# sc.net
KiCad netlist of a schematic drawn in EAGLE
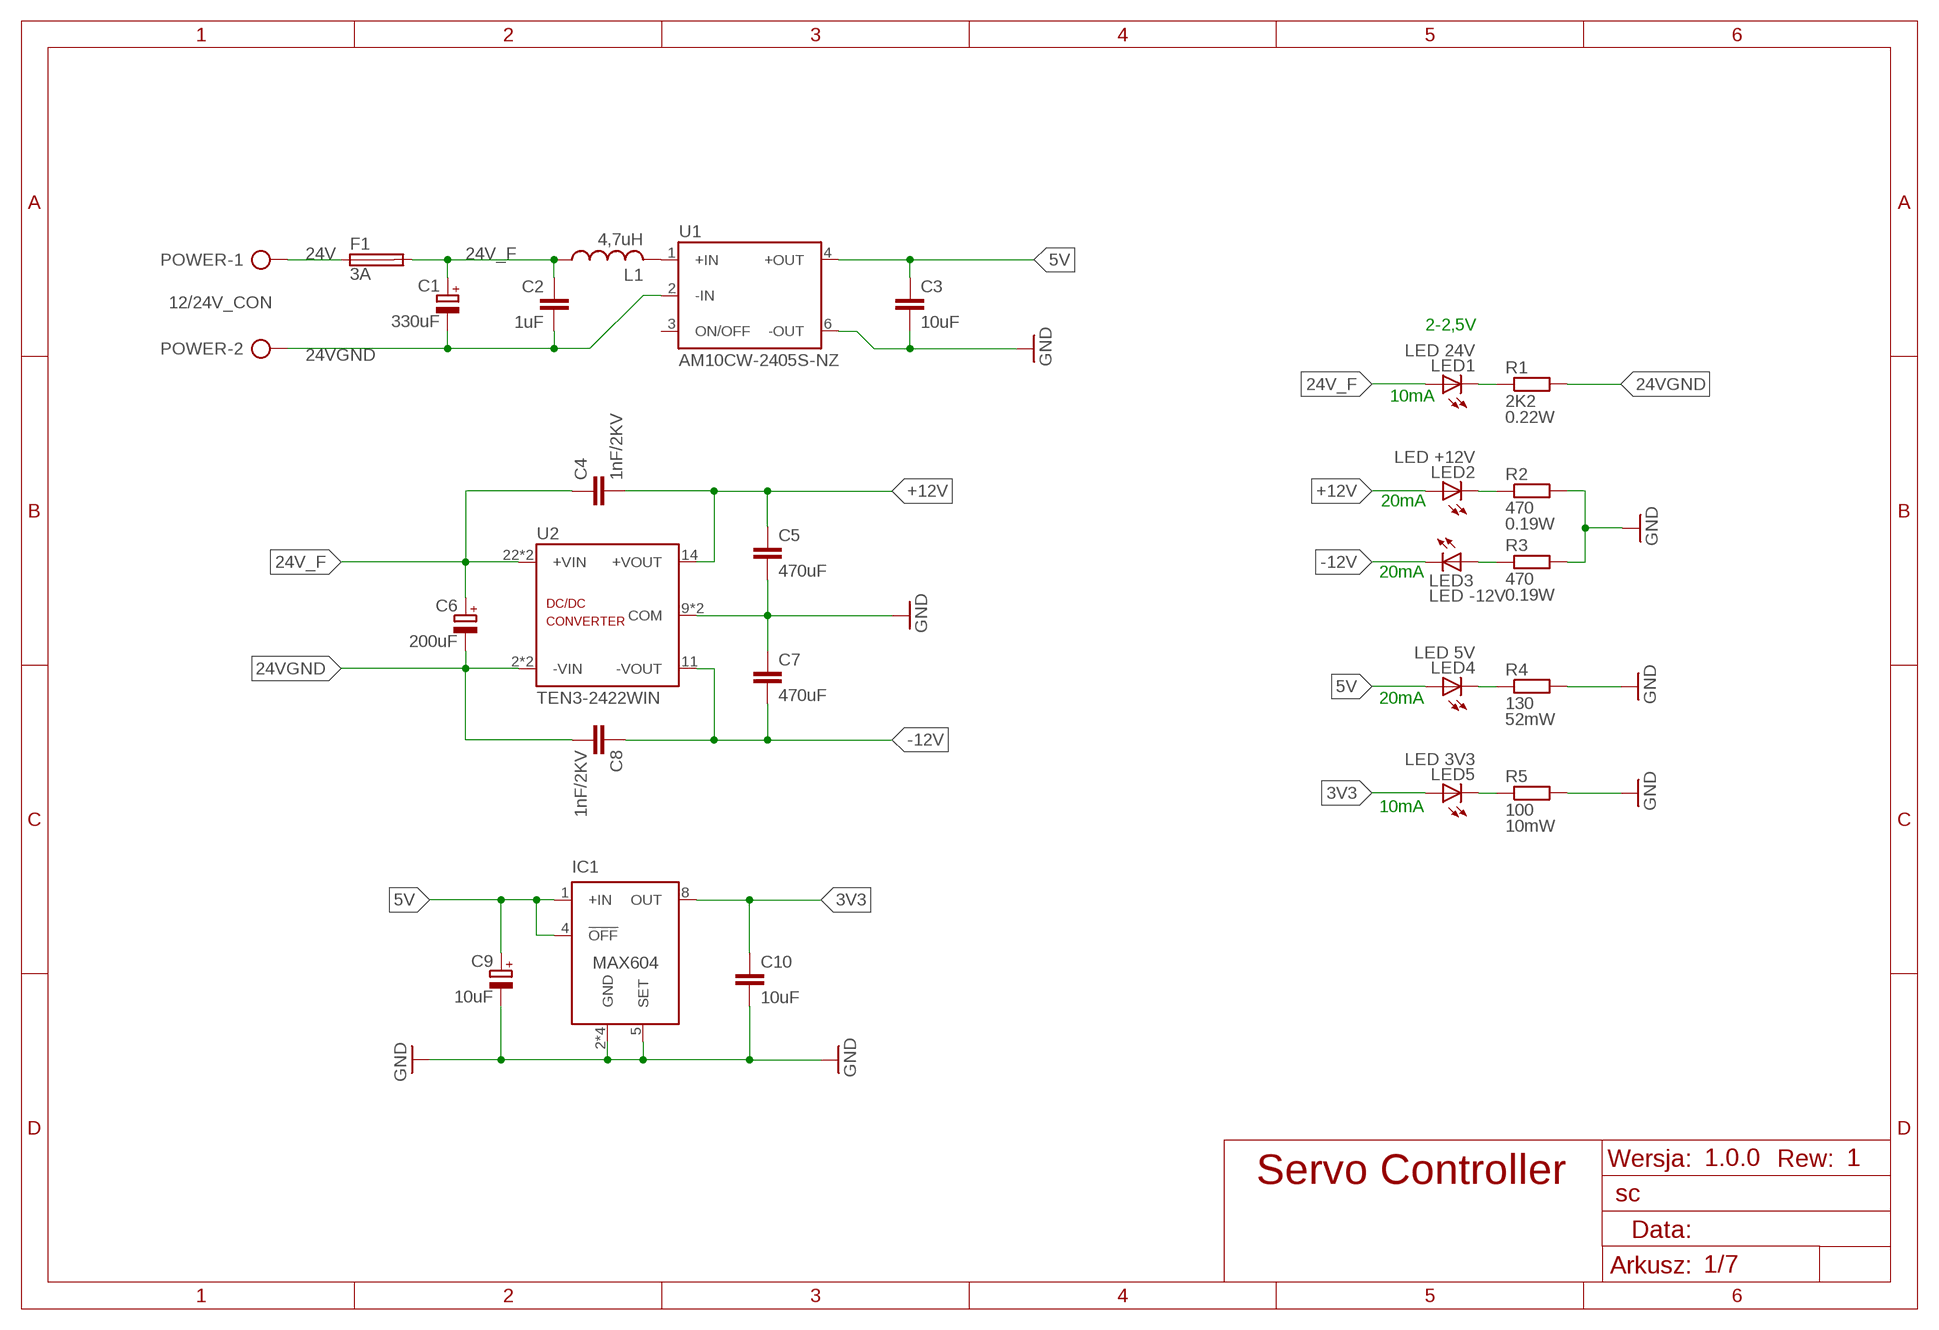
[diagram p0: schematic, sheet 1]
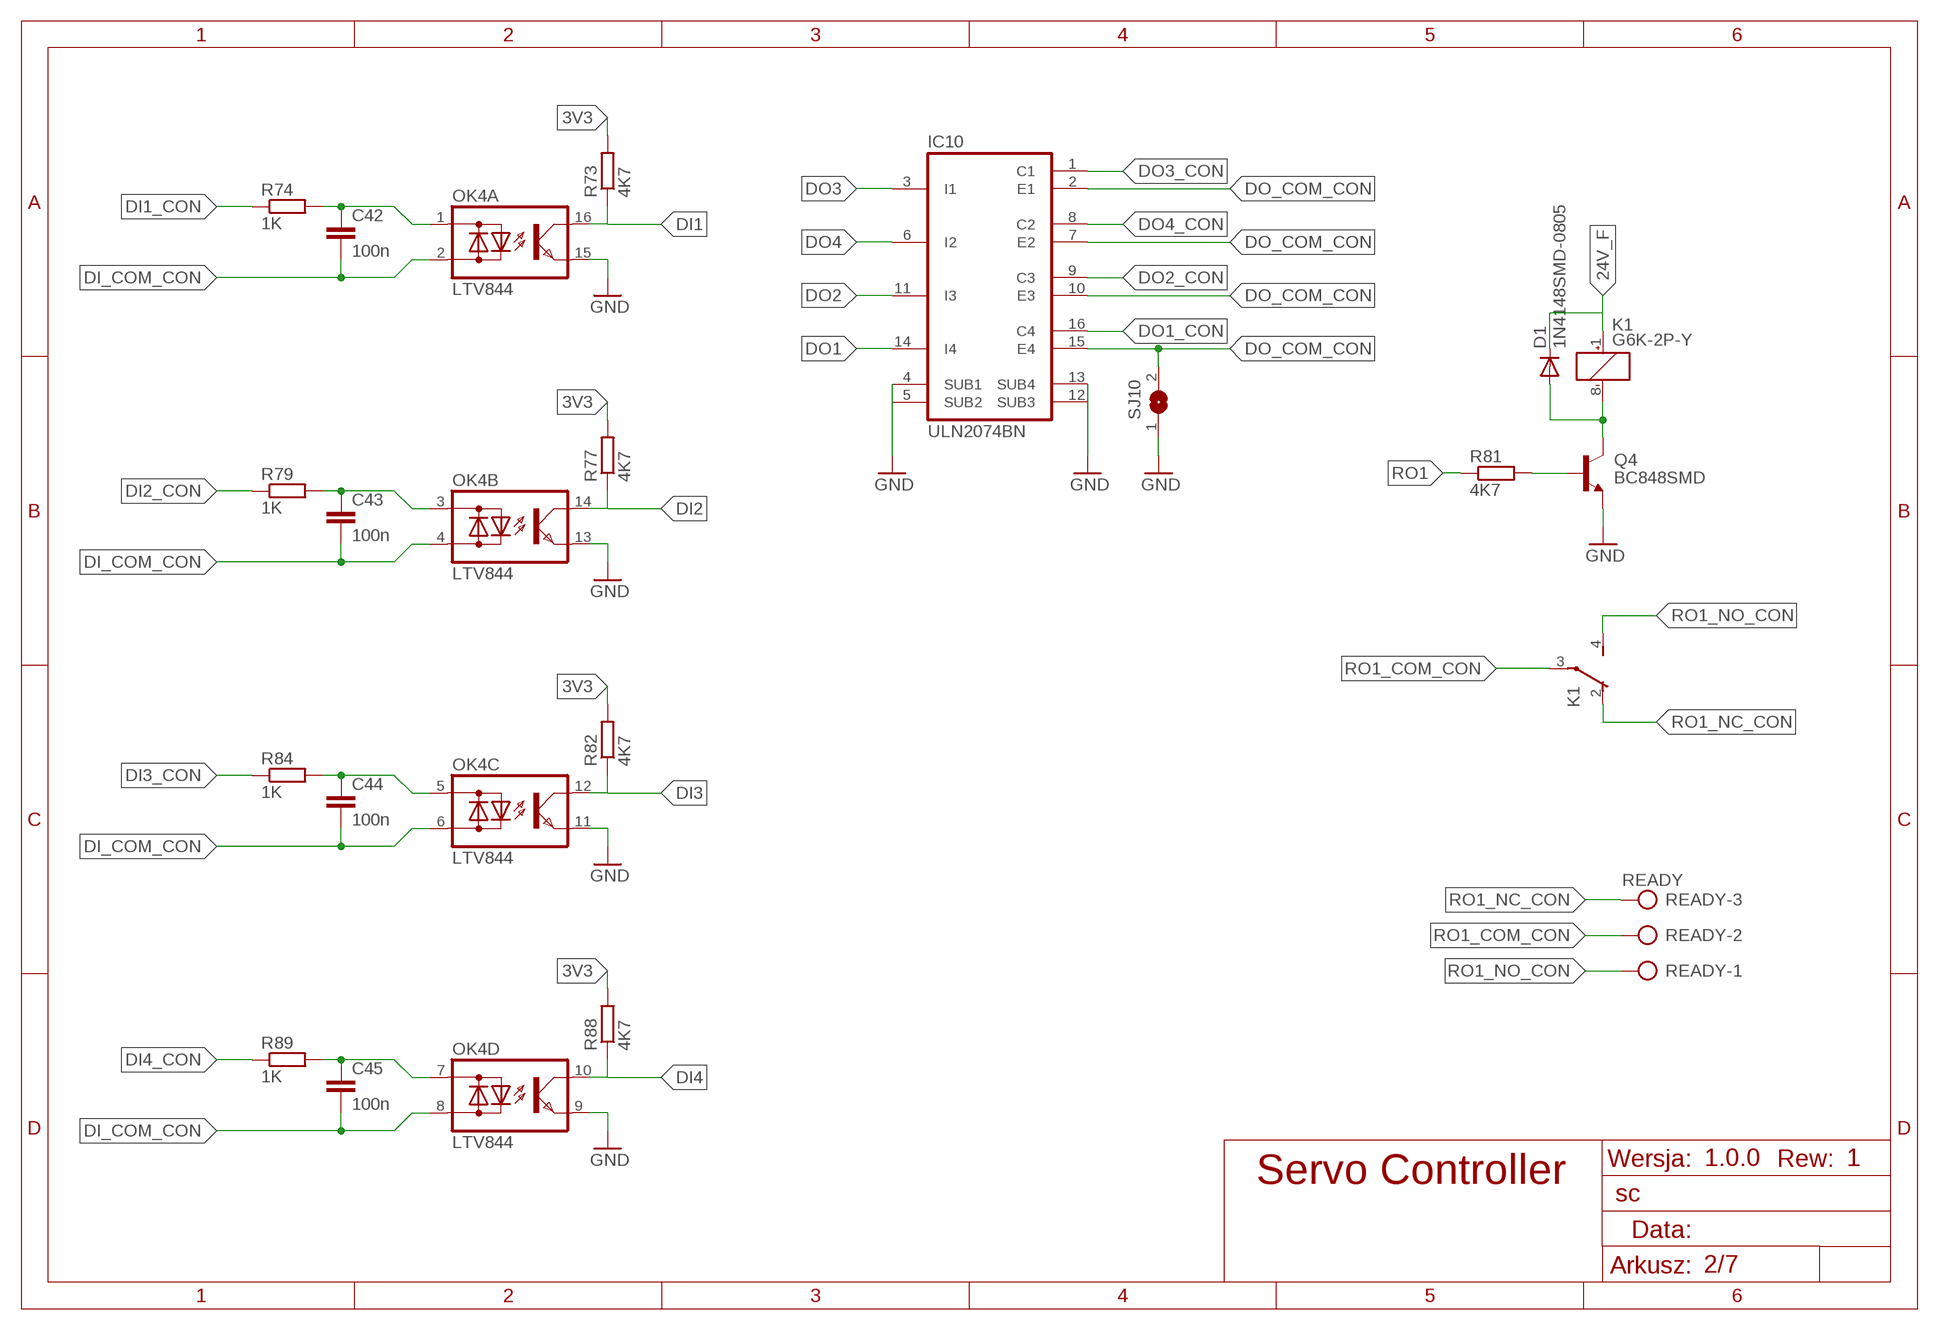
[diagram p1: schematic, sheet 2]
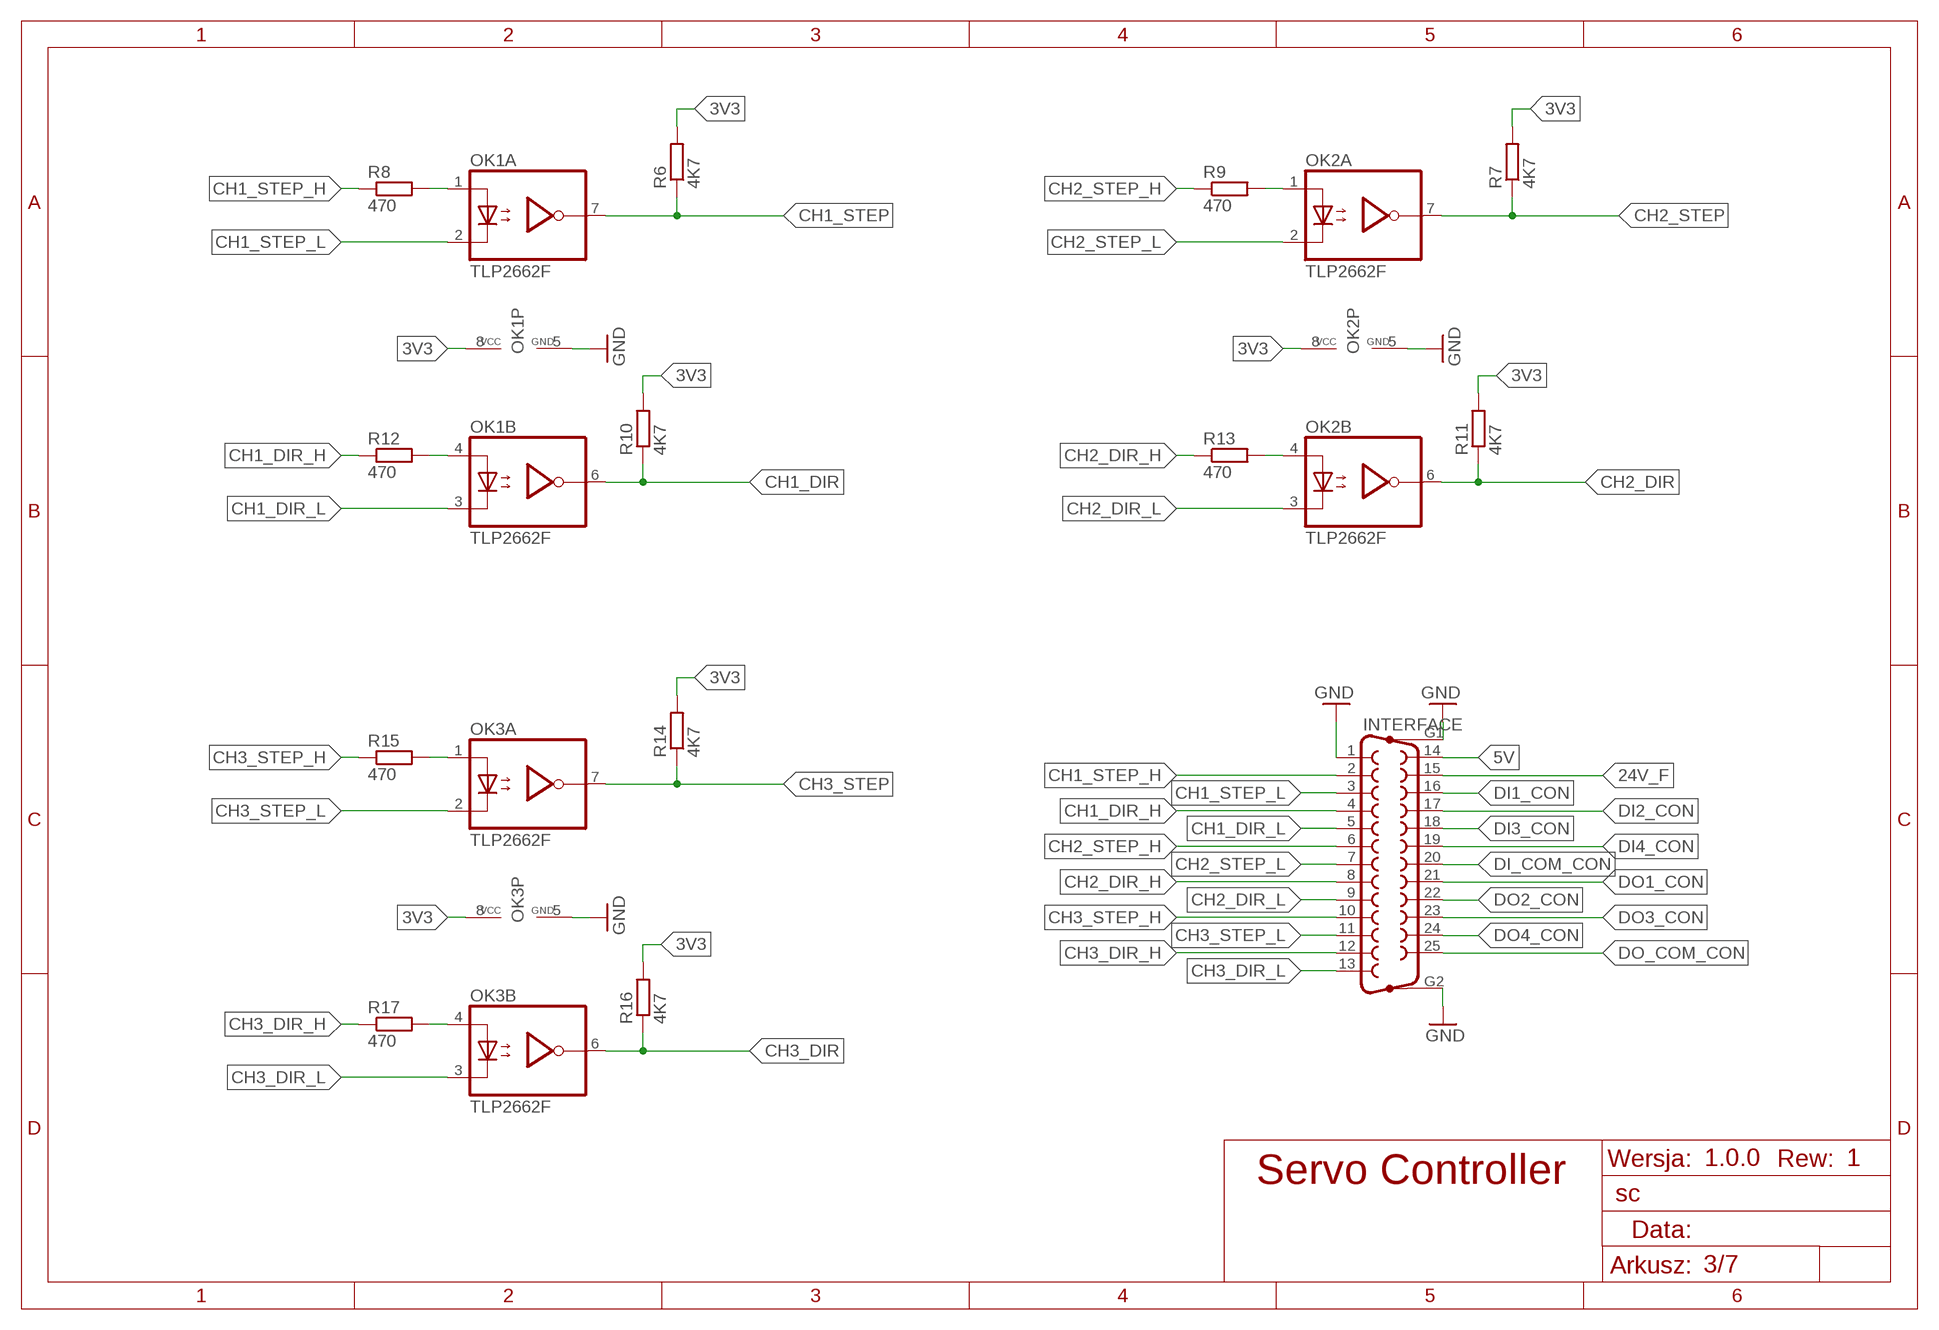
[diagram p2: schematic, sheet 3]
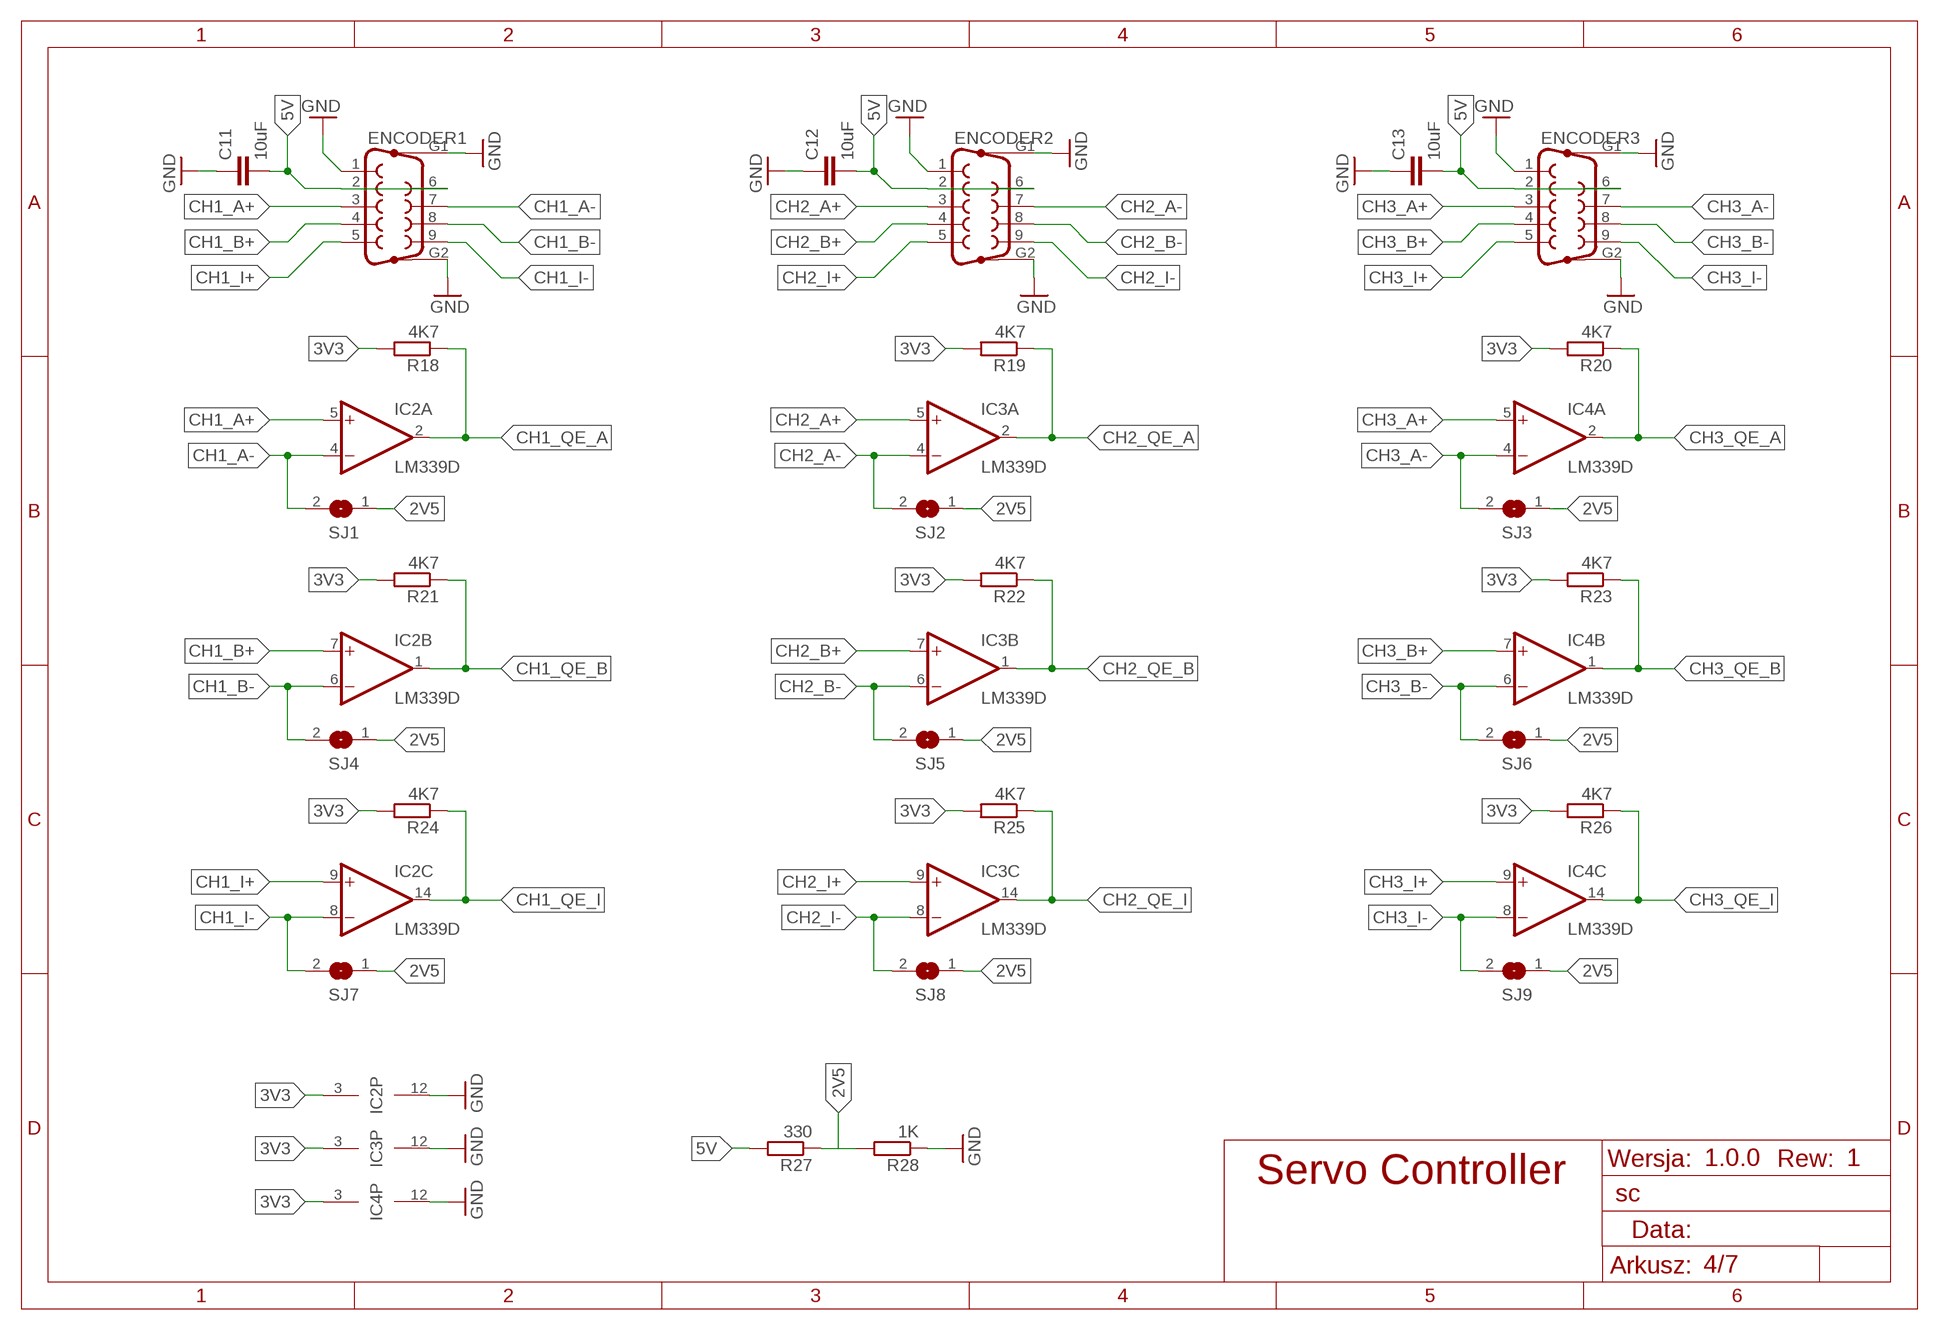
[diagram p3: schematic, sheet 4]
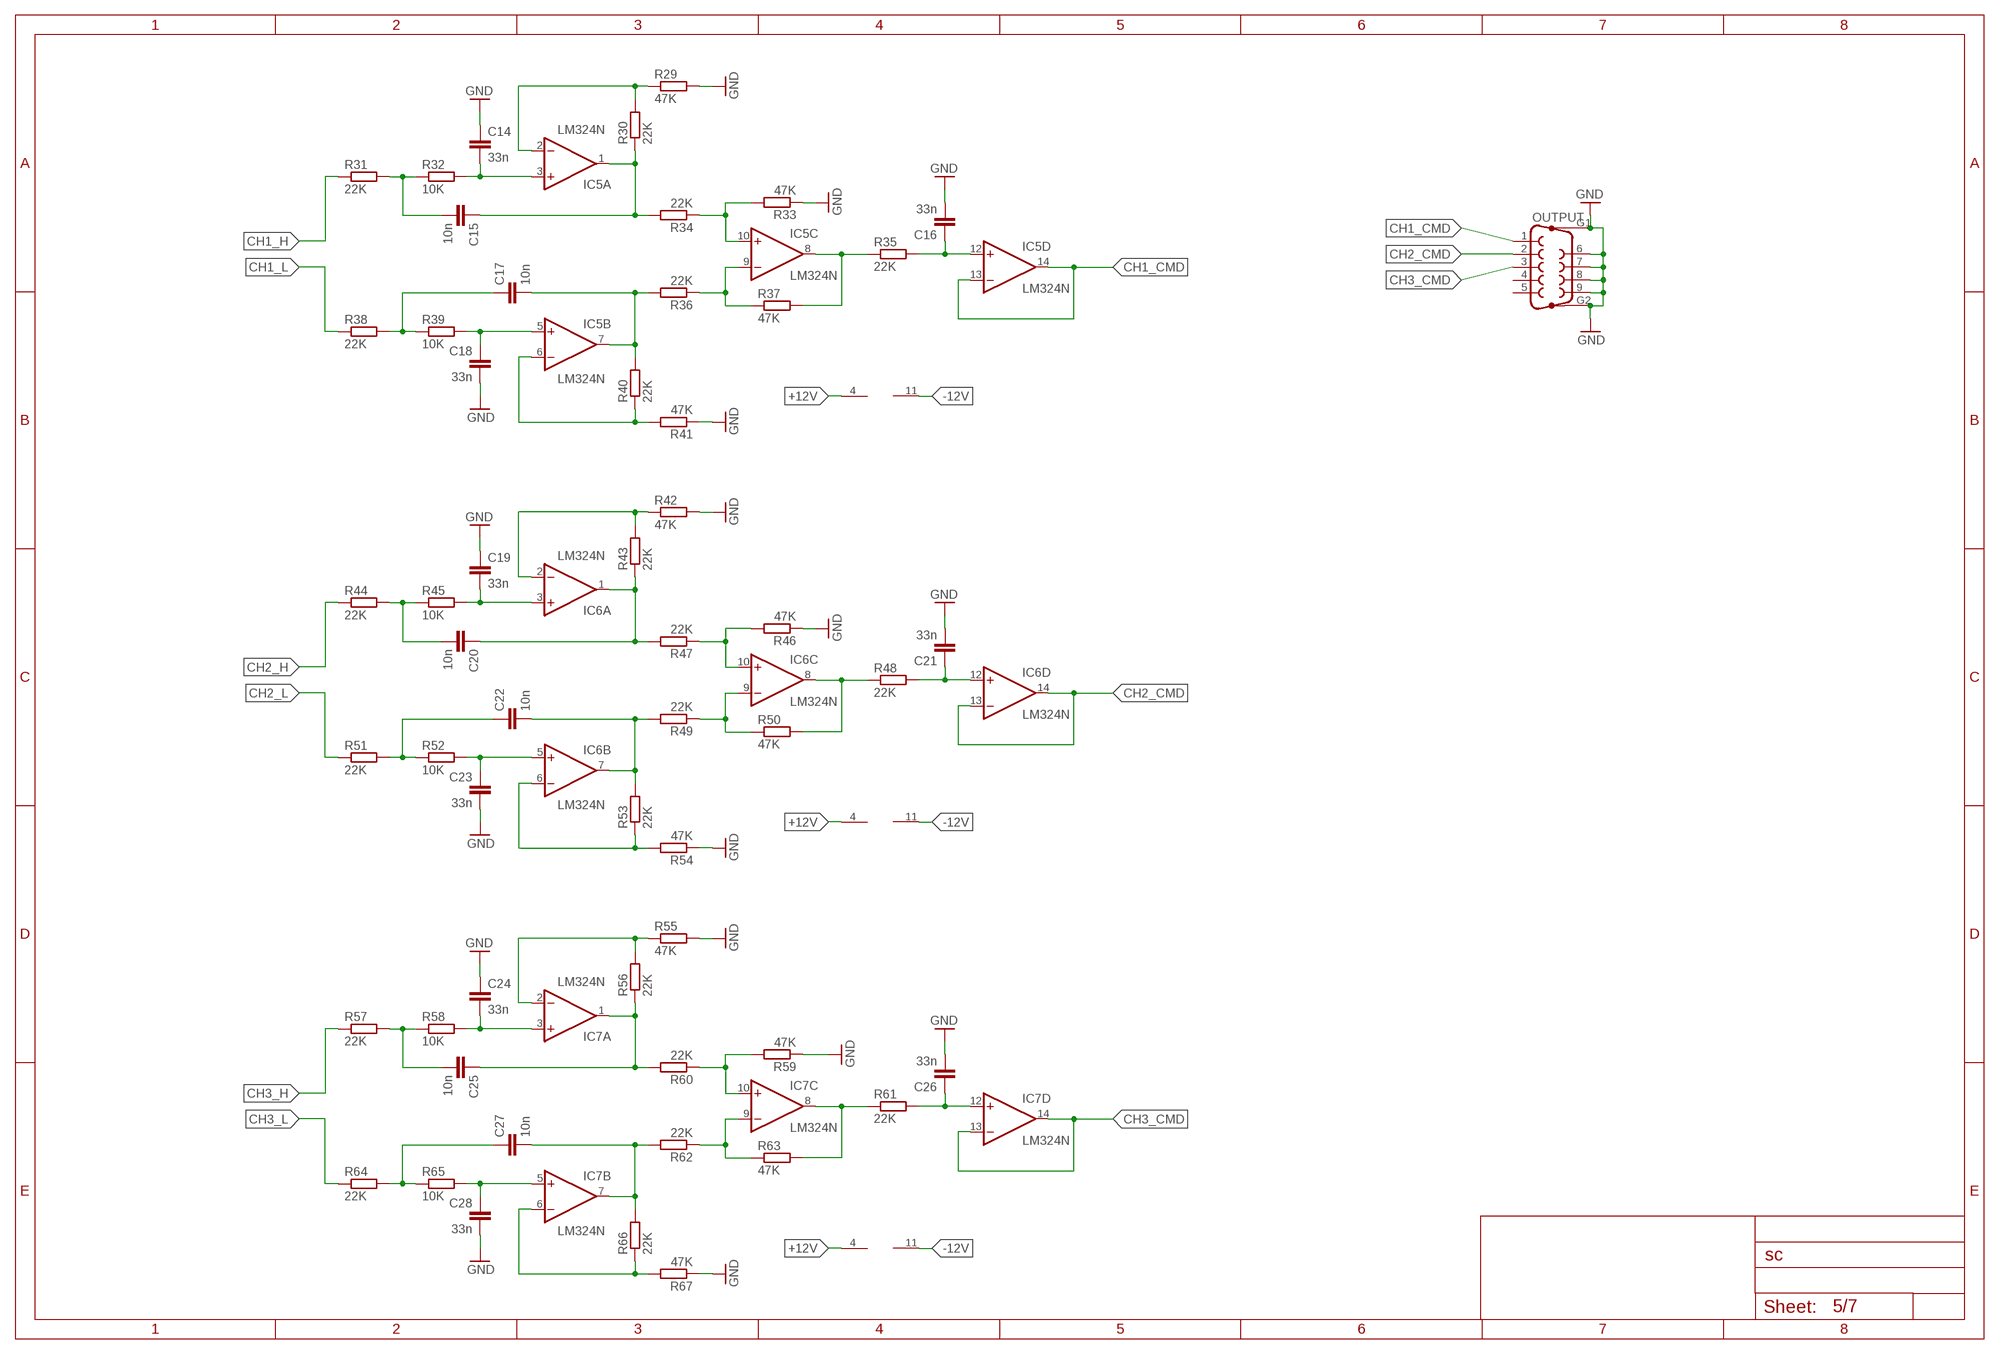
[diagram p4: schematic, sheet 5]
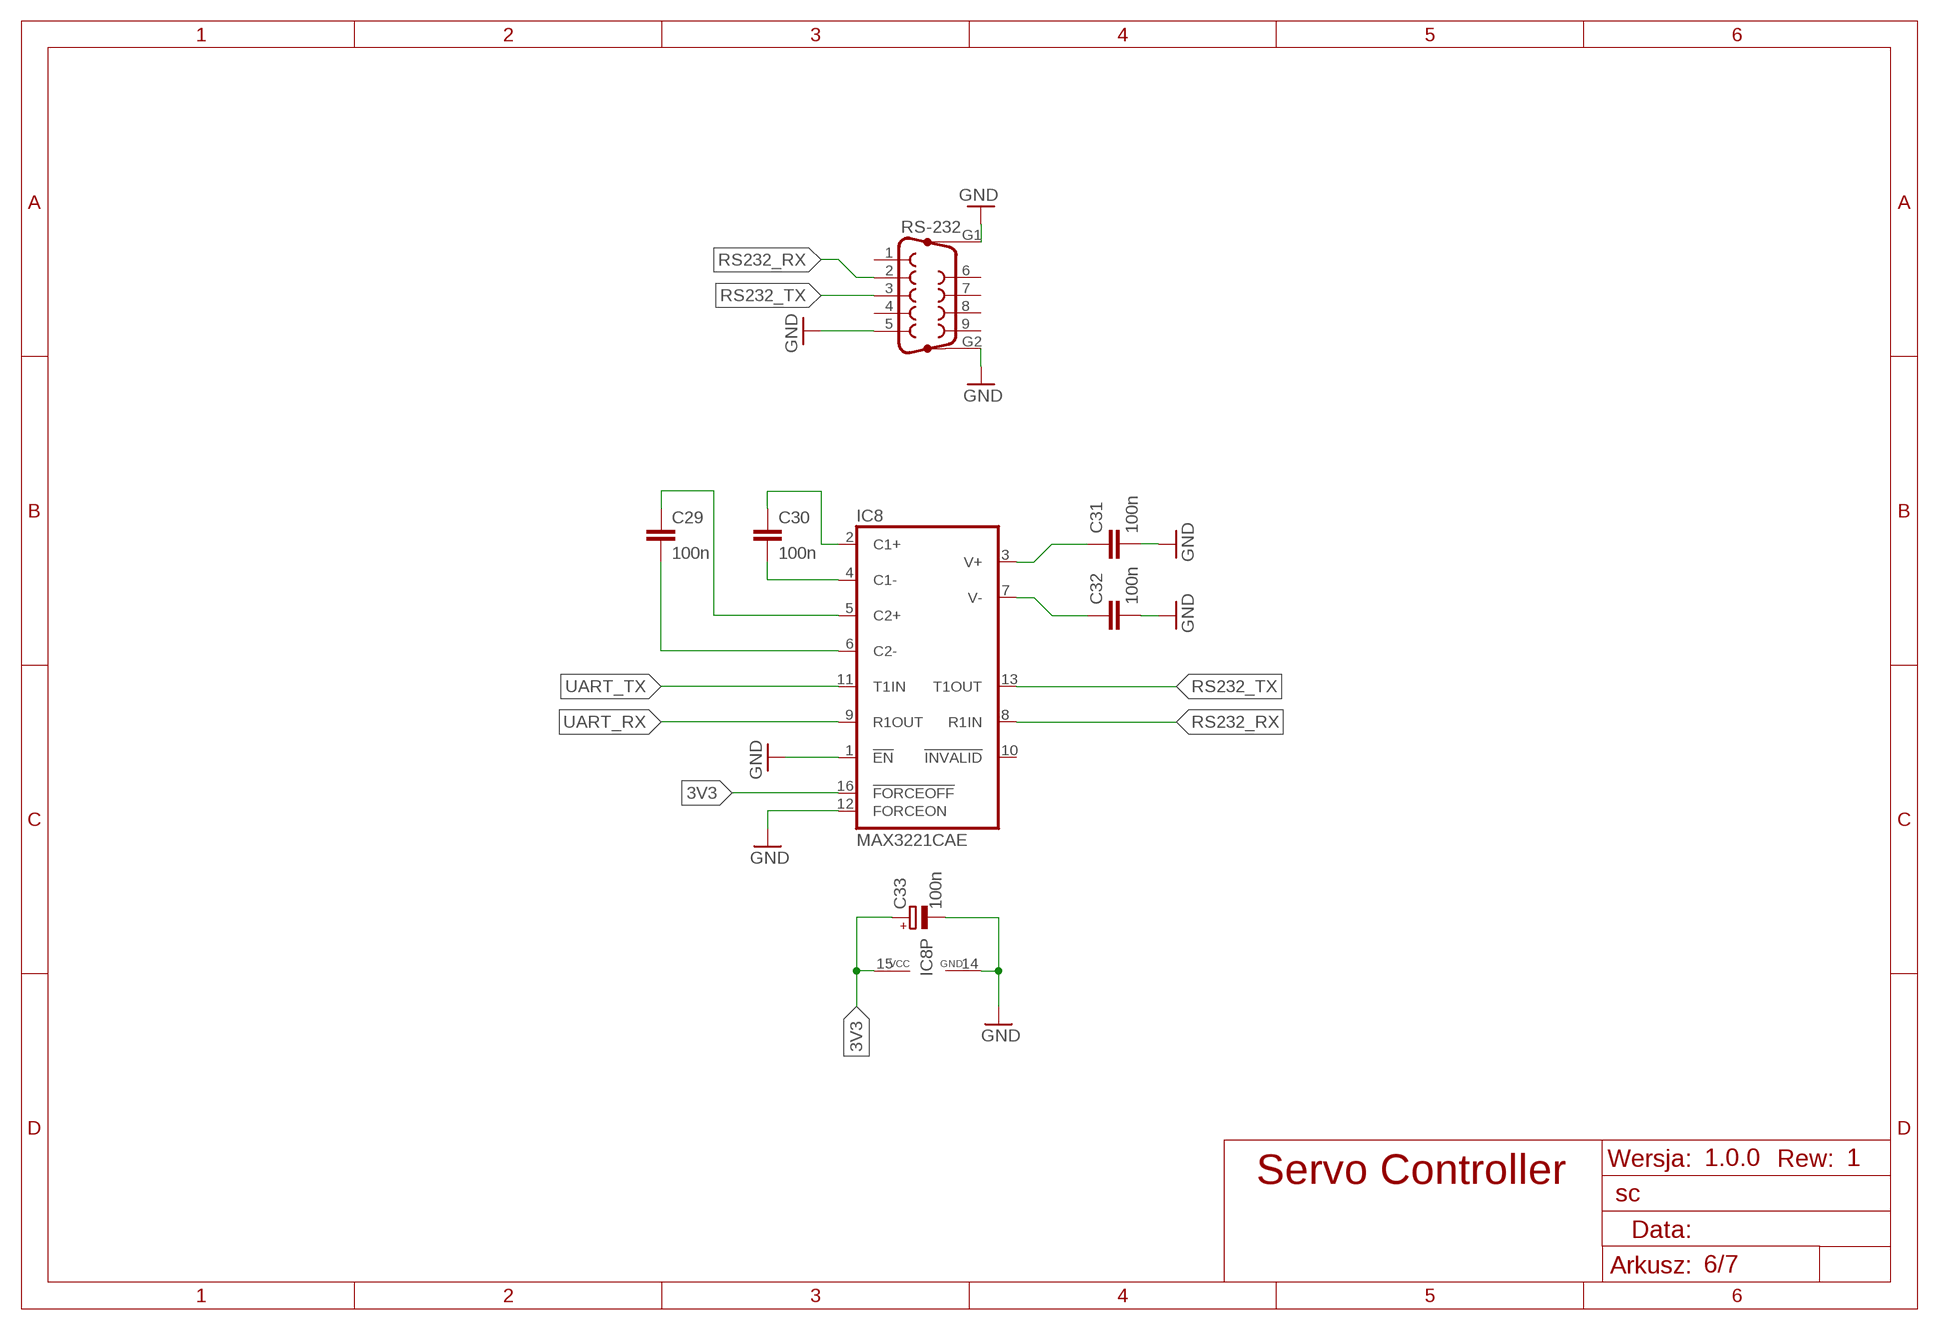
[diagram p5: schematic, sheet 6]
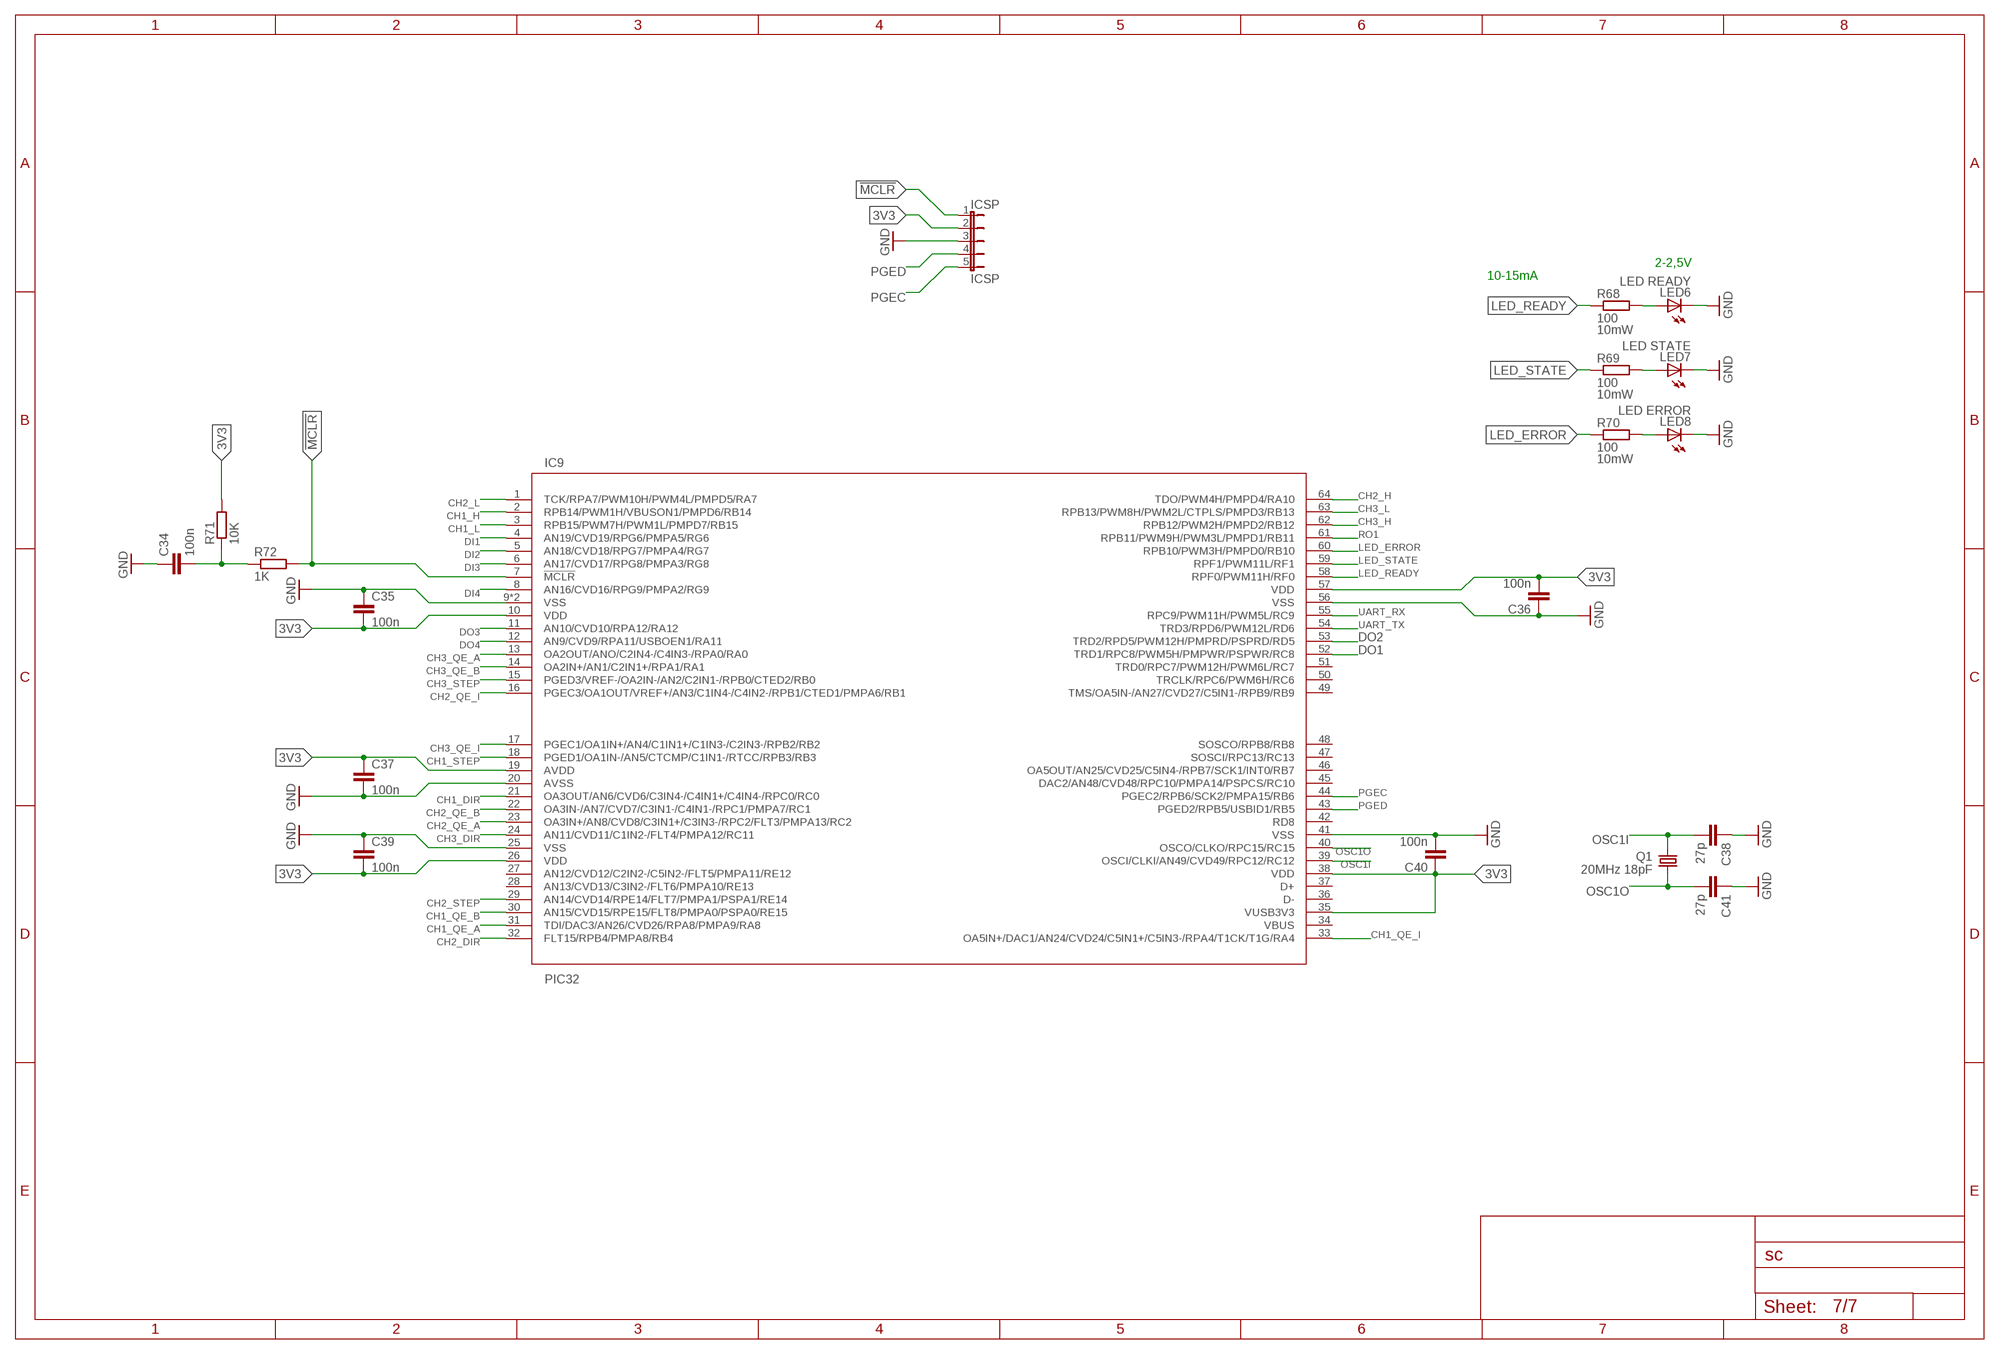
[diagram p6: schematic, sheet 7]

(export (version "E")
  (design (tool "Eeschema 10.0.6"))
  (components
    (comp (ref "C34")
      (value "100n")
      (footprint "eagle-import:C0805")
      (libsource (lib "eagle-import") (part "C-EUC0805"))
    )
    (comp (ref "C35")
      (value "100n")
      (footprint "eagle-import:C0805")
      (libsource (lib "eagle-import") (part "C-EUC0805"))
    )
    (comp (ref "C36")
      (value "100n")
      (footprint "eagle-import:C0805")
      (libsource (lib "eagle-import") (part "C-EUC0805"))
    )
    (comp (ref "C37")
      (value "100n")
      (footprint "eagle-import:C0805")
      (libsource (lib "eagle-import") (part "C-EUC0805"))
    )
    (comp (ref "C38")
      (value "27p")
      (footprint "eagle-import:C0805")
      (libsource (lib "eagle-import") (part "C-EUC0805"))
    )
    (comp (ref "C39")
      (value "100n")
      (footprint "eagle-import:C0805")
      (libsource (lib "eagle-import") (part "C-EUC0805"))
    )
    (comp (ref "C40")
      (value "100n")
      (footprint "eagle-import:C0805")
      (libsource (lib "eagle-import") (part "C-EUC0805"))
    )
    (comp (ref "C41")
      (value "27p")
      (footprint "eagle-import:C0805")
      (libsource (lib "eagle-import") (part "C-EUC0805"))
    )
    (comp (ref "IC9")
      (value "PIC32")
      (footprint "eagle-import:QFN64-9X9")
      (libsource (lib "eagle-import") (part "PIC32MK1024MCF0649X9MM"))
    )
    (comp (ref "ICSP")
      (value "ICSP")
      (footprint "eagle-import:JP5")
      (libsource (lib "eagle-import") (part "JP5E"))
    )
    (comp (ref "LED6")
      (value "LED READY")
      (footprint "eagle-import:SML1206")
      (libsource (lib "eagle-import") (part "LEDSML1206"))
    )
    (comp (ref "LED7")
      (value "LED STATE")
      (footprint "eagle-import:SML1206")
      (libsource (lib "eagle-import") (part "LEDSML1206"))
    )
    (comp (ref "LED8")
      (value "LED ERROR")
      (footprint "eagle-import:SML1206")
      (libsource (lib "eagle-import") (part "LEDSML1206"))
    )
    (comp (ref "Q1")
      (value "20MHz 18pF")
      (footprint "eagle-import:SM49")
      (libsource (lib "eagle-import") (part "CRYSTALSM49"))
    )
    (comp (ref "R68")
      (value "100")
      (footprint "eagle-import:R0805")
      (fields (field (name "POWER") "10mW"))
      (libsource (lib "eagle-import") (part "R-EU_R0805"))
    )
    (comp (ref "R69")
      (value "100")
      (footprint "eagle-import:R0805")
      (fields (field (name "POWER") "10mW"))
      (libsource (lib "eagle-import") (part "R-EU_R0805"))
    )
    (comp (ref "R70")
      (value "100")
      (footprint "eagle-import:R0805")
      (fields (field (name "POWER") "10mW"))
      (libsource (lib "eagle-import") (part "R-EU_R0805"))
    )
    (comp (ref "R71")
      (value "10K")
      (footprint "eagle-import:R0805")
      (libsource (lib "eagle-import") (part "R-EU_R0805"))
    )
    (comp (ref "R72")
      (value "1K")
      (footprint "eagle-import:R0805")
      (libsource (lib "eagle-import") (part "R-EU_R0805"))
    )
    (comp (ref "C1")
      (value "330uF")
      (footprint "eagle-import:E5-10,5")
      (libsource (lib "eagle-import") (part "CPOL-EUE5-10.5"))
    )
    (comp (ref "C2")
      (value "1uF")
      (footprint "eagle-import:C0805")
      (libsource (lib "eagle-import") (part "C-EUC0805"))
    )
    (comp (ref "C3")
      (value "10uF")
      (footprint "eagle-import:C0805")
      (libsource (lib "eagle-import") (part "C-EUC0805"))
    )
    (comp (ref "C4")
      (value "1nF/2KV")
      (footprint "eagle-import:C0805")
      (libsource (lib "eagle-import") (part "C-EUC0805"))
    )
    (comp (ref "C5")
      (value "470uF")
      (footprint "eagle-import:C0805")
      (libsource (lib "eagle-import") (part "C-EUC0805"))
    )
    (comp (ref "C6")
      (value "200uF")
      (footprint "eagle-import:E5-10,5")
      (libsource (lib "eagle-import") (part "CPOL-EUE5-10.5"))
    )
    (comp (ref "C7")
      (value "470uF")
      (footprint "eagle-import:C0805")
      (libsource (lib "eagle-import") (part "C-EUC0805"))
    )
    (comp (ref "C8")
      (value "1nF/2KV")
      (footprint "eagle-import:C0805")
      (libsource (lib "eagle-import") (part "C-EUC0805"))
    )
    (comp (ref "C9")
      (value "10uF")
      (footprint "eagle-import:UD-4X5,8_NICHICON")
      (libsource (lib "eagle-import") (part "CPOL-EUUD-4X5,8"))
    )
    (comp (ref "C10")
      (value "10uF")
      (footprint "eagle-import:C0805")
      (libsource (lib "eagle-import") (part "C-EUC0805"))
    )
    (comp (ref "F1")
      (value "3A")
      (footprint "eagle-import:SH22,5")
      (fields (field (name "MF") "SCHURTER") (field (name "MPN") "0031.8201"))
      (libsource (lib "eagle-import") (part "SH22,5"))
    )
    (comp (ref "IC1")
      (value "MAX604")
      (footprint "eagle-import:DIL08")
      (libsource (lib "eagle-import") (part "MAX604"))
    )
    (comp (ref "L1")
      (value "4,7uH")
      (footprint "eagle-import:DJNR6028")
      (libsource (lib "eagle-import") (part "DJNR6028--S"))
    )
    (comp (ref "LED1")
      (value "LED 24V")
      (footprint "eagle-import:SML1206")
      (libsource (lib "eagle-import") (part "LEDSML1206"))
    )
    (comp (ref "LED2")
      (value "LED +12V")
      (footprint "eagle-import:SML1206")
      (libsource (lib "eagle-import") (part "LEDSML1206"))
    )
    (comp (ref "LED3")
      (value "LED -12V")
      (footprint "eagle-import:SML1206")
      (libsource (lib "eagle-import") (part "LEDSML1206"))
    )
    (comp (ref "LED4")
      (value "LED 5V")
      (footprint "eagle-import:SML1206")
      (libsource (lib "eagle-import") (part "LEDSML1206"))
    )
    (comp (ref "LED5")
      (value "LED 3V3")
      (footprint "eagle-import:SML1206")
      (libsource (lib "eagle-import") (part "LEDSML1206"))
    )
    (comp (ref "POWER")
      (value "12/24V_CON")
      (footprint "eagle-import:AK500_2")
      (libsource (lib "eagle-import") (part "AK500/2"))
    )
    (comp (ref "R1")
      (value "2K2")
      (footprint "eagle-import:R1206")
      (fields (field (name "POWER") "0.22W"))
      (libsource (lib "eagle-import") (part "R-EU_R1206"))
    )
    (comp (ref "R2")
      (value "470")
      (footprint "eagle-import:R0805")
      (fields (field (name "POWER") "0.19W"))
      (libsource (lib "eagle-import") (part "R-EU_R0805"))
    )
    (comp (ref "R3")
      (value "470")
      (footprint "eagle-import:R0805")
      (fields (field (name "POWER") "0.19W"))
      (libsource (lib "eagle-import") (part "R-EU_R0805"))
    )
    (comp (ref "R4")
      (value "130")
      (footprint "eagle-import:R0805")
      (fields (field (name "POWER") "52mW"))
      (libsource (lib "eagle-import") (part "R-EU_R0805"))
    )
    (comp (ref "R5")
      (value "100")
      (footprint "eagle-import:R0805")
      (fields (field (name "POWER") "10mW"))
      (libsource (lib "eagle-import") (part "R-EU_R0805"))
    )
    (comp (ref "U1")
      (value "AM10CW-2405S-NZ")
      (footprint "eagle-import:AM10CW-NZ")
      (libsource (lib "eagle-import") (part "AM10CW-S-NZ2405"))
    )
    (comp (ref "U2")
      (value "TEN3-2422WIN")
      (footprint "eagle-import:TEN3-WIN")
      (libsource (lib "eagle-import") (part "TEN3-WIN2422"))
    )
    (comp (ref "INTERFACE")
      (value "F25VP")
      (footprint "eagle-import:F25VP")
      (libsource (lib "eagle-import") (part "F25VP"))
    )
    (comp (ref "OK1")
      (value "TLP2662F")
      (footprint "eagle-import:DIL08")
      (libsource (lib "eagle-import") (part "TLP2662F"))
    )
    (comp (ref "OK2")
      (value "TLP2662F")
      (footprint "eagle-import:DIL08")
      (libsource (lib "eagle-import") (part "TLP2662F"))
    )
    (comp (ref "OK3")
      (value "TLP2662F")
      (footprint "eagle-import:DIL08")
      (libsource (lib "eagle-import") (part "TLP2662F"))
    )
    (comp (ref "R6")
      (value "4K7")
      (footprint "eagle-import:R0805")
      (libsource (lib "eagle-import") (part "R-EU_R0805"))
    )
    (comp (ref "R7")
      (value "4K7")
      (footprint "eagle-import:R0805")
      (libsource (lib "eagle-import") (part "R-EU_R0805"))
    )
    (comp (ref "R8")
      (value "470")
      (footprint "eagle-import:R0805")
      (libsource (lib "eagle-import") (part "R-EU_R0805"))
    )
    (comp (ref "R9")
      (value "470")
      (footprint "eagle-import:R0805")
      (libsource (lib "eagle-import") (part "R-EU_R0805"))
    )
    (comp (ref "R10")
      (value "4K7")
      (footprint "eagle-import:R0805")
      (libsource (lib "eagle-import") (part "R-EU_R0805"))
    )
    (comp (ref "R11")
      (value "4K7")
      (footprint "eagle-import:R0805")
      (libsource (lib "eagle-import") (part "R-EU_R0805"))
    )
    (comp (ref "R12")
      (value "470")
      (footprint "eagle-import:R0805")
      (libsource (lib "eagle-import") (part "R-EU_R0805"))
    )
    (comp (ref "R13")
      (value "470")
      (footprint "eagle-import:R0805")
      (libsource (lib "eagle-import") (part "R-EU_R0805"))
    )
    (comp (ref "R14")
      (value "4K7")
      (footprint "eagle-import:R0805")
      (libsource (lib "eagle-import") (part "R-EU_R0805"))
    )
    (comp (ref "R15")
      (value "470")
      (footprint "eagle-import:R0805")
      (libsource (lib "eagle-import") (part "R-EU_R0805"))
    )
    (comp (ref "R16")
      (value "4K7")
      (footprint "eagle-import:R0805")
      (libsource (lib "eagle-import") (part "R-EU_R0805"))
    )
    (comp (ref "R17")
      (value "470")
      (footprint "eagle-import:R0805")
      (libsource (lib "eagle-import") (part "R-EU_R0805"))
    )
    (comp (ref "C11")
      (value "10uF")
      (footprint "eagle-import:C0805")
      (libsource (lib "eagle-import") (part "C-EUC0805"))
    )
    (comp (ref "C12")
      (value "10uF")
      (footprint "eagle-import:C0805")
      (libsource (lib "eagle-import") (part "C-EUC0805"))
    )
    (comp (ref "C13")
      (value "10uF")
      (footprint "eagle-import:C0805")
      (libsource (lib "eagle-import") (part "C-EUC0805"))
    )
    (comp (ref "ENCODER1")
      (value "F09VP")
      (footprint "eagle-import:F09VP")
      (libsource (lib "eagle-import") (part "F09VP"))
    )
    (comp (ref "ENCODER2")
      (value "F09VP")
      (footprint "eagle-import:F09VP")
      (libsource (lib "eagle-import") (part "F09VP"))
    )
    (comp (ref "ENCODER3")
      (value "F09VP")
      (footprint "eagle-import:F09VP")
      (libsource (lib "eagle-import") (part "F09VP"))
    )
    (comp (ref "IC2")
      (value "LM339D")
      (footprint "eagle-import:SO14")
      (libsource (lib "eagle-import") (part "LM339D"))
    )
    (comp (ref "IC3")
      (value "LM339D")
      (footprint "eagle-import:SO14")
      (libsource (lib "eagle-import") (part "LM339D"))
    )
    (comp (ref "IC4")
      (value "LM339D")
      (footprint "eagle-import:SO14")
      (libsource (lib "eagle-import") (part "LM339D"))
    )
    (comp (ref "R18")
      (value "4K7")
      (footprint "eagle-import:R0805")
      (libsource (lib "eagle-import") (part "R-EU_R0805"))
    )
    (comp (ref "R19")
      (value "4K7")
      (footprint "eagle-import:R0805")
      (libsource (lib "eagle-import") (part "R-EU_R0805"))
    )
    (comp (ref "R20")
      (value "4K7")
      (footprint "eagle-import:R0805")
      (libsource (lib "eagle-import") (part "R-EU_R0805"))
    )
    (comp (ref "R21")
      (value "4K7")
      (footprint "eagle-import:R0805")
      (libsource (lib "eagle-import") (part "R-EU_R0805"))
    )
    (comp (ref "R22")
      (value "4K7")
      (footprint "eagle-import:R0805")
      (libsource (lib "eagle-import") (part "R-EU_R0805"))
    )
    (comp (ref "R23")
      (value "4K7")
      (footprint "eagle-import:R0805")
      (libsource (lib "eagle-import") (part "R-EU_R0805"))
    )
    (comp (ref "R24")
      (value "4K7")
      (footprint "eagle-import:R0805")
      (libsource (lib "eagle-import") (part "R-EU_R0805"))
    )
    (comp (ref "R25")
      (value "4K7")
      (footprint "eagle-import:R0805")
      (libsource (lib "eagle-import") (part "R-EU_R0805"))
    )
    (comp (ref "R26")
      (value "4K7")
      (footprint "eagle-import:R0805")
      (libsource (lib "eagle-import") (part "R-EU_R0805"))
    )
    (comp (ref "R27")
      (value "330")
      (footprint "eagle-import:R0805")
      (libsource (lib "eagle-import") (part "R-EU_R0805"))
    )
    (comp (ref "R28")
      (value "1K")
      (footprint "eagle-import:R0805")
      (libsource (lib "eagle-import") (part "R-EU_R0805"))
    )
    (comp (ref "SJ1") (value "SJ") (footprint "eagle-import:SJ") (libsource (lib "eagle-import") (part "SJ")))
    (comp (ref "SJ2") (value "SJ") (footprint "eagle-import:SJ") (libsource (lib "eagle-import") (part "SJ")))
    (comp (ref "SJ3") (value "SJ") (footprint "eagle-import:SJ") (libsource (lib "eagle-import") (part "SJ")))
    (comp (ref "SJ4") (value "SJ") (footprint "eagle-import:SJ") (libsource (lib "eagle-import") (part "SJ")))
    (comp (ref "SJ5") (value "SJ") (footprint "eagle-import:SJ") (libsource (lib "eagle-import") (part "SJ")))
    (comp (ref "SJ6") (value "SJ") (footprint "eagle-import:SJ") (libsource (lib "eagle-import") (part "SJ")))
    (comp (ref "SJ7") (value "SJ") (footprint "eagle-import:SJ") (libsource (lib "eagle-import") (part "SJ")))
    (comp (ref "SJ8") (value "SJ") (footprint "eagle-import:SJ") (libsource (lib "eagle-import") (part "SJ")))
    (comp (ref "SJ9") (value "SJ") (footprint "eagle-import:SJ") (libsource (lib "eagle-import") (part "SJ")))
    (comp (ref "C29")
      (value "100n")
      (footprint "eagle-import:C0805")
      (libsource (lib "eagle-import") (part "C-EUC0805"))
    )
    (comp (ref "C30")
      (value "100n")
      (footprint "eagle-import:C0805")
      (libsource (lib "eagle-import") (part "C-EUC0805"))
    )
    (comp (ref "C31")
      (value "100n")
      (footprint "eagle-import:C0805")
      (libsource (lib "eagle-import") (part "C-EUC0805"))
    )
    (comp (ref "C32")
      (value "100n")
      (footprint "eagle-import:C0805")
      (libsource (lib "eagle-import") (part "C-EUC0805"))
    )
    (comp (ref "C33")
      (value "100n")
      (footprint "eagle-import:UD-4X5,8_NICHICON")
      (libsource (lib "eagle-import") (part "CPOL-EUUD-4X5,8"))
    )
    (comp (ref "IC8")
      (value "MAX3221CAE")
      (footprint "eagle-import:SSOP16")
      (fields (field (name "MF") "MAXIM") (field (name "MPN") "MAX3221CAE+"))
      (libsource (lib "eagle-import") (part "MAX3221AEC"))
    )
    (comp (ref "RS-232")
      (value "F09VP")
      (footprint "eagle-import:F09VP")
      (libsource (lib "eagle-import") (part "F09VP"))
    )
    (comp (ref "C42")
      (value "100n")
      (footprint "eagle-import:C0805")
      (libsource (lib "eagle-import") (part "C-EUC0805"))
    )
    (comp (ref "C43")
      (value "100n")
      (footprint "eagle-import:C0805")
      (libsource (lib "eagle-import") (part "C-EUC0805"))
    )
    (comp (ref "C44")
      (value "100n")
      (footprint "eagle-import:C0805")
      (libsource (lib "eagle-import") (part "C-EUC0805"))
    )
    (comp (ref "C45")
      (value "100n")
      (footprint "eagle-import:C0805")
      (libsource (lib "eagle-import") (part "C-EUC0805"))
    )
    (comp (ref "D1")
      (value "1N4148SMD-0805")
      (footprint "eagle-import:D0805")
      (libsource (lib "eagle-import") (part "1N4148SMD-0805"))
    )
    (comp (ref "IC10")
      (value "ULN2074BN")
      (footprint "eagle-import:DIL16")
      (libsource (lib "eagle-import") (part "ULN2074BN"))
    )
    (comp (ref "K1")
      (value "G6K-2P-Y")
      (footprint "eagle-import:G6K-2P-Y")
      (fields (field (name "MF") "OMRON COMPONENTS USA") (field (name "MPN") "G6K-2P-Y DC12"))
      (libsource (lib "eagle-import") (part "G6K-2P-Y"))
    )
    (comp (ref "OK4")
      (value "LTV844")
      (footprint "eagle-import:DIL16")
      (libsource (lib "eagle-import") (part "LTV844"))
    )
    (comp (ref "Q4")
      (value "BC848SMD")
      (footprint "eagle-import:SOT23")
      (libsource (lib "eagle-import") (part "BC848SMD"))
    )
    (comp (ref "R73")
      (value "4K7")
      (footprint "eagle-import:R0805")
      (libsource (lib "eagle-import") (part "R-EU_R0805"))
    )
    (comp (ref "R74")
      (value "1K")
      (footprint "eagle-import:R0805")
      (libsource (lib "eagle-import") (part "R-EU_R0805"))
    )
    (comp (ref "R77")
      (value "4K7")
      (footprint "eagle-import:R0805")
      (libsource (lib "eagle-import") (part "R-EU_R0805"))
    )
    (comp (ref "R79")
      (value "1K")
      (footprint "eagle-import:R0805")
      (libsource (lib "eagle-import") (part "R-EU_R0805"))
    )
    (comp (ref "R81")
      (value "4K7")
      (footprint "eagle-import:R0805")
      (libsource (lib "eagle-import") (part "R-EU_R0805"))
    )
    (comp (ref "R82")
      (value "4K7")
      (footprint "eagle-import:R0805")
      (libsource (lib "eagle-import") (part "R-EU_R0805"))
    )
    (comp (ref "R84")
      (value "1K")
      (footprint "eagle-import:R0805")
      (libsource (lib "eagle-import") (part "R-EU_R0805"))
    )
    (comp (ref "R88")
      (value "4K7")
      (footprint "eagle-import:R0805")
      (libsource (lib "eagle-import") (part "R-EU_R0805"))
    )
    (comp (ref "R89")
      (value "1K")
      (footprint "eagle-import:R0805")
      (libsource (lib "eagle-import") (part "R-EU_R0805"))
    )
    (comp (ref "READY")
      (value "READY")
      (footprint "eagle-import:AK500_3")
      (libsource (lib "eagle-import") (part "AK500/3"))
    )
    (comp (ref "SJ10")
      (value "SJ")
      (footprint "eagle-import:SJ")
      (libsource (lib "eagle-import") (part "SJ"))
    )
    (comp (ref "C14")
      (value "33n")
      (footprint "eagle-import:C0805")
      (libsource (lib "eagle-import") (part "C-EUC0805"))
    )
    (comp (ref "C15")
      (value "10n")
      (footprint "eagle-import:C0805")
      (libsource (lib "eagle-import") (part "C-EUC0805"))
    )
    (comp (ref "C16")
      (value "33n")
      (footprint "eagle-import:C0805")
      (libsource (lib "eagle-import") (part "C-EUC0805"))
    )
    (comp (ref "C17")
      (value "10n")
      (footprint "eagle-import:C0805")
      (libsource (lib "eagle-import") (part "C-EUC0805"))
    )
    (comp (ref "C18")
      (value "33n")
      (footprint "eagle-import:C0805")
      (libsource (lib "eagle-import") (part "C-EUC0805"))
    )
    (comp (ref "C19")
      (value "33n")
      (footprint "eagle-import:C0805")
      (libsource (lib "eagle-import") (part "C-EUC0805"))
    )
    (comp (ref "C20")
      (value "10n")
      (footprint "eagle-import:C0805")
      (libsource (lib "eagle-import") (part "C-EUC0805"))
    )
    (comp (ref "C21")
      (value "33n")
      (footprint "eagle-import:C0805")
      (libsource (lib "eagle-import") (part "C-EUC0805"))
    )
    (comp (ref "C22")
      (value "10n")
      (footprint "eagle-import:C0805")
      (libsource (lib "eagle-import") (part "C-EUC0805"))
    )
    (comp (ref "C23")
      (value "33n")
      (footprint "eagle-import:C0805")
      (libsource (lib "eagle-import") (part "C-EUC0805"))
    )
    (comp (ref "C24")
      (value "33n")
      (footprint "eagle-import:C0805")
      (libsource (lib "eagle-import") (part "C-EUC0805"))
    )
    (comp (ref "C25")
      (value "10n")
      (footprint "eagle-import:C0805")
      (libsource (lib "eagle-import") (part "C-EUC0805"))
    )
    (comp (ref "C26")
      (value "33n")
      (footprint "eagle-import:C0805")
      (libsource (lib "eagle-import") (part "C-EUC0805"))
    )
    (comp (ref "C27")
      (value "10n")
      (footprint "eagle-import:C0805")
      (libsource (lib "eagle-import") (part "C-EUC0805"))
    )
    (comp (ref "C28")
      (value "33n")
      (footprint "eagle-import:C0805")
      (libsource (lib "eagle-import") (part "C-EUC0805"))
    )
    (comp (ref "IC5")
      (value "LM324N")
      (footprint "eagle-import:DIL14")
      (libsource (lib "eagle-import") (part "LM324N"))
    )
    (comp (ref "IC6")
      (value "LM324N")
      (footprint "eagle-import:DIL14")
      (libsource (lib "eagle-import") (part "LM324N"))
    )
    (comp (ref "IC7")
      (value "LM324N")
      (footprint "eagle-import:DIL14")
      (libsource (lib "eagle-import") (part "LM324N"))
    )
    (comp (ref "OUTPUT")
      (value "F09VP")
      (footprint "eagle-import:F09VP")
      (libsource (lib "eagle-import") (part "F09VP"))
    )
    (comp (ref "R29")
      (value "47K")
      (footprint "eagle-import:R0805")
      (libsource (lib "eagle-import") (part "R-EU_R0805"))
    )
    (comp (ref "R30")
      (value "22K")
      (footprint "eagle-import:R0805")
      (libsource (lib "eagle-import") (part "R-EU_R0805"))
    )
    (comp (ref "R31")
      (value "22K")
      (footprint "eagle-import:R0805")
      (libsource (lib "eagle-import") (part "R-EU_R0805"))
    )
    (comp (ref "R32")
      (value "10K")
      (footprint "eagle-import:R0805")
      (libsource (lib "eagle-import") (part "R-EU_R0805"))
    )
    (comp (ref "R33")
      (value "47K")
      (footprint "eagle-import:R0805")
      (libsource (lib "eagle-import") (part "R-EU_R0805"))
    )
    (comp (ref "R34")
      (value "22K")
      (footprint "eagle-import:R0805")
      (libsource (lib "eagle-import") (part "R-EU_R0805"))
    )
    (comp (ref "R35")
      (value "22K")
      (footprint "eagle-import:R0805")
      (libsource (lib "eagle-import") (part "R-EU_R0805"))
    )
    (comp (ref "R36")
      (value "22K")
      (footprint "eagle-import:R0805")
      (libsource (lib "eagle-import") (part "R-EU_R0805"))
    )
    (comp (ref "R37")
      (value "47K")
      (footprint "eagle-import:R0805")
      (libsource (lib "eagle-import") (part "R-EU_R0805"))
    )
    (comp (ref "R38")
      (value "22K")
      (footprint "eagle-import:R0805")
      (libsource (lib "eagle-import") (part "R-EU_R0805"))
    )
    (comp (ref "R39")
      (value "10K")
      (footprint "eagle-import:R0805")
      (libsource (lib "eagle-import") (part "R-EU_R0805"))
    )
    (comp (ref "R40")
      (value "22K")
      (footprint "eagle-import:R0805")
      (libsource (lib "eagle-import") (part "R-EU_R0805"))
    )
    (comp (ref "R41")
      (value "47K")
      (footprint "eagle-import:R0805")
      (libsource (lib "eagle-import") (part "R-EU_R0805"))
    )
    (comp (ref "R42")
      (value "47K")
      (footprint "eagle-import:R0805")
      (libsource (lib "eagle-import") (part "R-EU_R0805"))
    )
    (comp (ref "R43")
      (value "22K")
      (footprint "eagle-import:R0805")
      (libsource (lib "eagle-import") (part "R-EU_R0805"))
    )
    (comp (ref "R44")
      (value "22K")
      (footprint "eagle-import:R0805")
      (libsource (lib "eagle-import") (part "R-EU_R0805"))
    )
    (comp (ref "R45")
      (value "10K")
      (footprint "eagle-import:R0805")
      (libsource (lib "eagle-import") (part "R-EU_R0805"))
    )
    (comp (ref "R46")
      (value "47K")
      (footprint "eagle-import:R0805")
      (libsource (lib "eagle-import") (part "R-EU_R0805"))
    )
    (comp (ref "R47")
      (value "22K")
      (footprint "eagle-import:R0805")
      (libsource (lib "eagle-import") (part "R-EU_R0805"))
    )
    (comp (ref "R48")
      (value "22K")
      (footprint "eagle-import:R0805")
      (libsource (lib "eagle-import") (part "R-EU_R0805"))
    )
    (comp (ref "R49")
      (value "22K")
      (footprint "eagle-import:R0805")
      (libsource (lib "eagle-import") (part "R-EU_R0805"))
    )
    (comp (ref "R50")
      (value "47K")
      (footprint "eagle-import:R0805")
      (libsource (lib "eagle-import") (part "R-EU_R0805"))
    )
    (comp (ref "R51")
      (value "22K")
      (footprint "eagle-import:R0805")
      (libsource (lib "eagle-import") (part "R-EU_R0805"))
    )
    (comp (ref "R52")
      (value "10K")
      (footprint "eagle-import:R0805")
      (libsource (lib "eagle-import") (part "R-EU_R0805"))
    )
    (comp (ref "R53")
      (value "22K")
      (footprint "eagle-import:R0805")
      (libsource (lib "eagle-import") (part "R-EU_R0805"))
    )
    (comp (ref "R54")
      (value "47K")
      (footprint "eagle-import:R0805")
      (libsource (lib "eagle-import") (part "R-EU_R0805"))
    )
    (comp (ref "R55")
      (value "47K")
      (footprint "eagle-import:R0805")
      (libsource (lib "eagle-import") (part "R-EU_R0805"))
    )
    (comp (ref "R56")
      (value "22K")
      (footprint "eagle-import:R0805")
      (libsource (lib "eagle-import") (part "R-EU_R0805"))
    )
    (comp (ref "R57")
      (value "22K")
      (footprint "eagle-import:R0805")
      (libsource (lib "eagle-import") (part "R-EU_R0805"))
    )
    (comp (ref "R58")
      (value "10K")
      (footprint "eagle-import:R0805")
      (libsource (lib "eagle-import") (part "R-EU_R0805"))
    )
    (comp (ref "R59")
      (value "47K")
      (footprint "eagle-import:R0805")
      (libsource (lib "eagle-import") (part "R-EU_R0805"))
    )
    (comp (ref "R60")
      (value "22K")
      (footprint "eagle-import:R0805")
      (libsource (lib "eagle-import") (part "R-EU_R0805"))
    )
    (comp (ref "R61")
      (value "22K")
      (footprint "eagle-import:R0805")
      (libsource (lib "eagle-import") (part "R-EU_R0805"))
    )
    (comp (ref "R62")
      (value "22K")
      (footprint "eagle-import:R0805")
      (libsource (lib "eagle-import") (part "R-EU_R0805"))
    )
    (comp (ref "R63")
      (value "47K")
      (footprint "eagle-import:R0805")
      (libsource (lib "eagle-import") (part "R-EU_R0805"))
    )
    (comp (ref "R64")
      (value "22K")
      (footprint "eagle-import:R0805")
      (libsource (lib "eagle-import") (part "R-EU_R0805"))
    )
    (comp (ref "R65")
      (value "10K")
      (footprint "eagle-import:R0805")
      (libsource (lib "eagle-import") (part "R-EU_R0805"))
    )
    (comp (ref "R66")
      (value "22K")
      (footprint "eagle-import:R0805")
      (libsource (lib "eagle-import") (part "R-EU_R0805"))
    )
    (comp (ref "R67")
      (value "47K")
      (footprint "eagle-import:R0805")
      (libsource (lib "eagle-import") (part "R-EU_R0805"))
    )
  )
  (nets
    (net (code "1") (name "+12V") (class "Default")
      (node (ref "C4") (pin "2") (pinfunction "2_2") (pintype "passive"))
      (node (ref "C5") (pin "1") (pinfunction "1_1") (pintype "passive"))
      (node (ref "IC5") (pin "4") (pinfunction "V+_4") (pintype "power_in"))
      (node (ref "IC6") (pin "4") (pinfunction "V+_4") (pintype "power_in"))
      (node (ref "IC7") (pin "4") (pinfunction "V+_4") (pintype "power_in"))
      (node (ref "LED2") (pin "A") (pinfunction "A_A") (pintype "passive"))
      (node (ref "U2") (pin "14") (pinfunction "+VOUT_14") (pintype "passive"))
    )
    (net (code "2") (name "-12V") (class "Default")
      (node (ref "C7") (pin "2") (pinfunction "2_2") (pintype "passive"))
      (node (ref "C8") (pin "1") (pinfunction "1_1") (pintype "passive"))
      (node (ref "IC5") (pin "11") (pinfunction "V-_11") (pintype "power_in"))
      (node (ref "IC6") (pin "11") (pinfunction "V-_11") (pintype "power_in"))
      (node (ref "IC7") (pin "11") (pinfunction "V-_11") (pintype "power_in"))
      (node (ref "LED3") (pin "C") (pinfunction "C_C") (pintype "passive"))
      (node (ref "U2") (pin "11") (pinfunction "-VOUT_11") (pintype "passive"))
    )
    (net (code "3") (name "2V5") (class "Default")
      (node (ref "R27") (pin "1") (pinfunction "1_1") (pintype "passive"))
      (node (ref "R28") (pin "2") (pinfunction "2_2") (pintype "passive"))
      (node (ref "SJ1") (pin "1") (pinfunction "1_1") (pintype "passive"))
      (node (ref "SJ2") (pin "1") (pinfunction "1_1") (pintype "passive"))
      (node (ref "SJ3") (pin "1") (pinfunction "1_1") (pintype "passive"))
      (node (ref "SJ4") (pin "1") (pinfunction "1_1") (pintype "passive"))
      (node (ref "SJ5") (pin "1") (pinfunction "1_1") (pintype "passive"))
      (node (ref "SJ6") (pin "1") (pinfunction "1_1") (pintype "passive"))
      (node (ref "SJ7") (pin "1") (pinfunction "1_1") (pintype "passive"))
      (node (ref "SJ8") (pin "1") (pinfunction "1_1") (pintype "passive"))
      (node (ref "SJ9") (pin "1") (pinfunction "1_1") (pintype "passive"))
    )
    (net (code "4") (name "3V3") (class "Default")
      (node (ref "C10") (pin "1") (pinfunction "1_1") (pintype "passive"))
      (node (ref "C33") (pin "+") (pinfunction "+_+") (pintype "passive"))
      (node (ref "C35") (pin "2") (pinfunction "2_2") (pintype "passive"))
      (node (ref "C36") (pin "2") (pinfunction "2_2") (pintype "passive"))
      (node (ref "C37") (pin "1") (pinfunction "1_1") (pintype "passive"))
      (node (ref "C39") (pin "2") (pinfunction "2_2") (pintype "passive"))
      (node (ref "C40") (pin "1") (pinfunction "1_1") (pintype "passive"))
      (node (ref "IC1") (pin "8") (pinfunction "OUT_8") (pintype "output"))
      (node (ref "IC2") (pin "3") (pinfunction "V+_3") (pintype "power_in"))
      (node (ref "IC3") (pin "3") (pinfunction "V+_3") (pintype "power_in"))
      (node (ref "IC4") (pin "3") (pinfunction "V+_3") (pintype "power_in"))
      (node (ref "IC8") (pin "15") (pinfunction "VCC_15") (pintype "power_in"))
      (node (ref "IC8") (pin "16") (pinfunction "~{FORCEOFF}_16") (pintype "input"))
      (node (ref "IC9") (pin "10") (pinfunction "VDD_10") (pintype "power_in"))
      (node (ref "IC9") (pin "19") (pinfunction "AVDD_19") (pintype "power_in"))
      (node (ref "IC9") (pin "26") (pinfunction "VDD_26") (pintype "power_in"))
      (node (ref "IC9") (pin "35") (pinfunction "VUSB3V3_35") (pintype "bidirectional"))
      (node (ref "IC9") (pin "38") (pinfunction "VDD_38") (pintype "power_in"))
      (node (ref "IC9") (pin "57") (pinfunction "VDD_57") (pintype "passive"))
      (node (ref "ICSP") (pin "2") (pinfunction "2_2") (pintype "passive"))
      (node (ref "LED5") (pin "A") (pinfunction "A_A") (pintype "passive"))
      (node (ref "OK1") (pin "8") (pinfunction "VCC_8") (pintype "power_in"))
      (node (ref "OK2") (pin "8") (pinfunction "VCC_8") (pintype "power_in"))
      (node (ref "OK3") (pin "8") (pinfunction "VCC_8") (pintype "power_in"))
      (node (ref "R10") (pin "2") (pinfunction "2_2") (pintype "passive"))
      (node (ref "R11") (pin "2") (pinfunction "2_2") (pintype "passive"))
      (node (ref "R14") (pin "2") (pinfunction "2_2") (pintype "passive"))
      (node (ref "R16") (pin "2") (pinfunction "2_2") (pintype "passive"))
      (node (ref "R18") (pin "2") (pinfunction "2_2") (pintype "passive"))
      (node (ref "R19") (pin "2") (pinfunction "2_2") (pintype "passive"))
      (node (ref "R20") (pin "2") (pinfunction "2_2") (pintype "passive"))
      (node (ref "R21") (pin "2") (pinfunction "2_2") (pintype "passive"))
      (node (ref "R22") (pin "2") (pinfunction "2_2") (pintype "passive"))
      (node (ref "R23") (pin "2") (pinfunction "2_2") (pintype "passive"))
      (node (ref "R24") (pin "2") (pinfunction "2_2") (pintype "passive"))
      (node (ref "R25") (pin "2") (pinfunction "2_2") (pintype "passive"))
      (node (ref "R26") (pin "2") (pinfunction "2_2") (pintype "passive"))
      (node (ref "R6") (pin "2") (pinfunction "2_2") (pintype "passive"))
      (node (ref "R7") (pin "2") (pinfunction "2_2") (pintype "passive"))
      (node (ref "R71") (pin "2") (pinfunction "2_2") (pintype "passive"))
      (node (ref "R73") (pin "2") (pinfunction "2_2") (pintype "passive"))
      (node (ref "R77") (pin "2") (pinfunction "2_2") (pintype "passive"))
      (node (ref "R82") (pin "2") (pinfunction "2_2") (pintype "passive"))
      (node (ref "R88") (pin "2") (pinfunction "2_2") (pintype "passive"))
    )
    (net (code "5") (name "5V") (class "Default")
      (node (ref "C11") (pin "2") (pinfunction "2_2") (pintype "passive"))
      (node (ref "C12") (pin "2") (pinfunction "2_2") (pintype "passive"))
      (node (ref "C13") (pin "2") (pinfunction "2_2") (pintype "passive"))
      (node (ref "C3") (pin "1") (pinfunction "1_1") (pintype "passive"))
      (node (ref "C9") (pin "+") (pinfunction "+_+") (pintype "passive"))
      (node (ref "ENCODER1") (pin "2") (pinfunction "2_2") (pintype "passive"))
      (node (ref "ENCODER1") (pin "6") (pinfunction "6_6") (pintype "passive"))
      (node (ref "ENCODER2") (pin "2") (pinfunction "2_2") (pintype "passive"))
      (node (ref "ENCODER2") (pin "6") (pinfunction "6_6") (pintype "passive"))
      (node (ref "ENCODER3") (pin "2") (pinfunction "2_2") (pintype "passive"))
      (node (ref "ENCODER3") (pin "6") (pinfunction "6_6") (pintype "passive"))
      (node (ref "IC1") (pin "1") (pinfunction "+IN_1") (pintype "power_in"))
      (node (ref "IC1") (pin "4") (pinfunction "~{OFF}_4") (pintype "input"))
      (node (ref "INTERFACE") (pin "14") (pinfunction "14_14") (pintype "passive"))
      (node (ref "LED4") (pin "A") (pinfunction "A_A") (pintype "passive"))
      (node (ref "R27") (pin "2") (pinfunction "2_2") (pintype "passive"))
      (node (ref "U1") (pin "4") (pinfunction "+OUT_4") (pintype "output"))
    )
    (net (code "6") (name "24V") (class "Default")
      (node (ref "F1") (pin "1") (pinfunction "1_1") (pintype "passive"))
      (node (ref "POWER") (pin "1") (pinfunction "KL_1") (pintype "passive"))
    )
    (net (code "7") (name "24VGND") (class "Default")
      (node (ref "C1") (pin "-") (pinfunction "-_-") (pintype "passive"))
      (node (ref "C2") (pin "2") (pinfunction "2_2") (pintype "passive"))
      (node (ref "C6") (pin "-") (pinfunction "-_-") (pintype "passive"))
      (node (ref "C8") (pin "2") (pinfunction "2_2") (pintype "passive"))
      (node (ref "POWER") (pin "2") (pinfunction "KL_2") (pintype "passive"))
      (node (ref "R1") (pin "2") (pinfunction "2_2") (pintype "passive"))
      (node (ref "U1") (pin "2") (pinfunction "-IN_2") (pintype "input"))
      (node (ref "U2") (pin "2") (pinfunction "-VIN_2") (pintype "passive"))
      (node (ref "U2") (pin "3") (pinfunction "-VIN_3") (pintype "passive"))
    )
    (net (code "8") (name "24V_F") (class "Default")
      (node (ref "C1") (pin "+") (pinfunction "+_+") (pintype "passive"))
      (node (ref "C2") (pin "1") (pinfunction "1_1") (pintype "passive"))
      (node (ref "C4") (pin "1") (pinfunction "1_1") (pintype "passive"))
      (node (ref "C6") (pin "+") (pinfunction "+_+") (pintype "passive"))
      (node (ref "D1") (pin "2") (pinfunction "C_2") (pintype "passive"))
      (node (ref "F1") (pin "2") (pinfunction "2_2") (pintype "passive"))
      (node (ref "INTERFACE") (pin "15") (pinfunction "15_15") (pintype "passive"))
      (node (ref "K1") (pin "1") (pinfunction "+_1") (pintype "passive"))
      (node (ref "L1") (pin "A") (pinfunction "1_A") (pintype "passive"))
      (node (ref "LED1") (pin "A") (pinfunction "A_A") (pintype "passive"))
      (node (ref "U2") (pin "22") (pinfunction "+VIN_22") (pintype "passive"))
      (node (ref "U2") (pin "23") (pinfunction "+VIN_23") (pintype "passive"))
    )
    (net (code "9") (name "CH1_A+") (class "Default")
      (node (ref "ENCODER1") (pin "3") (pinfunction "3_3") (pintype "passive"))
      (node (ref "IC2") (pin "5") (pinfunction "+IN_5") (pintype "input"))
    )
    (net (code "10") (name "CH1_A-") (class "Default")
      (node (ref "ENCODER1") (pin "7") (pinfunction "7_7") (pintype "passive"))
      (node (ref "IC2") (pin "4") (pinfunction "-IN_4") (pintype "input"))
      (node (ref "SJ1") (pin "2") (pinfunction "2_2") (pintype "passive"))
    )
    (net (code "11") (name "CH1_B+") (class "Default")
      (node (ref "ENCODER1") (pin "4") (pinfunction "4_4") (pintype "passive"))
      (node (ref "IC2") (pin "7") (pinfunction "+IN_7") (pintype "input"))
    )
    (net (code "12") (name "CH1_B-") (class "Default")
      (node (ref "ENCODER1") (pin "8") (pinfunction "8_8") (pintype "passive"))
      (node (ref "IC2") (pin "6") (pinfunction "-IN_6") (pintype "input"))
      (node (ref "SJ4") (pin "2") (pinfunction "2_2") (pintype "passive"))
    )
    (net (code "13") (name "CH1_CMD") (class "Default")
      (node (ref "IC5") (pin "13") (pinfunction "-IN_13") (pintype "input"))
      (node (ref "IC5") (pin "14") (pinfunction "OUT_14") (pintype "output"))
      (node (ref "OUTPUT") (pin "1") (pinfunction "1_1") (pintype "passive"))
    )
    (net (code "14") (name "CH1_DIR") (class "Default")
      (node (ref "IC9") (pin "21") (pinfunction "OA3OUT/AN6/CVD6/C3IN4-/C4IN1+/C4IN4-/RPC0/RC0_21") (pintype "bidirectional"))
      (node (ref "OK1") (pin "6") (pinfunction "VO_6") (pintype "passive"))
      (node (ref "R10") (pin "1") (pinfunction "1_1") (pintype "passive"))
    )
    (net (code "15") (name "CH1_DIR_H") (class "Default")
      (node (ref "INTERFACE") (pin "4") (pinfunction "4_4") (pintype "passive"))
      (node (ref "R12") (pin "1") (pinfunction "1_1") (pintype "passive"))
    )
    (net (code "16") (name "CH1_DIR_L") (class "Default")
      (node (ref "INTERFACE") (pin "5") (pinfunction "5_5") (pintype "passive"))
      (node (ref "OK1") (pin "3") (pinfunction "C_3") (pintype "passive"))
    )
    (net (code "17") (name "CH1_H") (class "Default")
      (node (ref "IC9") (pin "2") (pinfunction "RPB14/PWM1H/VBUSON1/PMPD6/RB14_2") (pintype "bidirectional"))
      (node (ref "R31") (pin "1") (pinfunction "1_1") (pintype "passive"))
    )
    (net (code "18") (name "CH1_I+") (class "Default")
      (node (ref "ENCODER1") (pin "5") (pinfunction "5_5") (pintype "passive"))
      (node (ref "IC2") (pin "9") (pinfunction "+IN_9") (pintype "input"))
    )
    (net (code "19") (name "CH1_I-") (class "Default")
      (node (ref "ENCODER1") (pin "9") (pinfunction "9_9") (pintype "passive"))
      (node (ref "IC2") (pin "8") (pinfunction "-IN_8") (pintype "input"))
      (node (ref "SJ7") (pin "2") (pinfunction "2_2") (pintype "passive"))
    )
    (net (code "20") (name "CH1_L") (class "Default")
      (node (ref "IC9") (pin "3") (pinfunction "RPB15/PWM7H/PWM1L/PMPD7/RB15_3") (pintype "bidirectional"))
      (node (ref "R38") (pin "1") (pinfunction "1_1") (pintype "passive"))
    )
    (net (code "21") (name "CH1_QE_A") (class "Default")
      (node (ref "IC2") (pin "2") (pinfunction "OUT_2") (pintype "open_collector"))
      (node (ref "IC9") (pin "31") (pinfunction "TDI/DAC3/AN26/CVD26/RPA8/PMPA9/RA8_31") (pintype "bidirectional"))
      (node (ref "R18") (pin "1") (pinfunction "1_1") (pintype "passive"))
    )
    (net (code "22") (name "CH1_QE_B") (class "Default")
      (node (ref "IC2") (pin "1") (pinfunction "OUT_1") (pintype "open_collector"))
      (node (ref "IC9") (pin "30") (pinfunction "AN15/CVD15/RPE15/FLT8/PMPA0/PSPA0/RE15_30") (pintype "bidirectional"))
      (node (ref "R21") (pin "1") (pinfunction "1_1") (pintype "passive"))
    )
    (net (code "23") (name "CH1_QE_I") (class "Default")
      (node (ref "IC2") (pin "14") (pinfunction "OUT_14") (pintype "open_collector"))
      (node (ref "IC9") (pin "33") (pinfunction "OA5IN+/DAC1/AN24/CVD24/C5IN1+/C5IN3-/RPA4/T1CK/T1G/RA4_33") (pintype "bidirectional"))
      (node (ref "R24") (pin "1") (pinfunction "1_1") (pintype "passive"))
    )
    (net (code "24") (name "CH1_STEP") (class "Default")
      (node (ref "IC9") (pin "18") (pinfunction "PGED1/OA1IN-/AN5/CTCMP/C1IN1-/RTCC/RPB3/RB3_18") (pintype "bidirectional"))
      (node (ref "OK1") (pin "7") (pinfunction "VO_7") (pintype "passive"))
      (node (ref "R6") (pin "1") (pinfunction "1_1") (pintype "passive"))
    )
    (net (code "25") (name "CH1_STEP_H") (class "Default")
      (node (ref "INTERFACE") (pin "2") (pinfunction "2_2") (pintype "passive"))
      (node (ref "R8") (pin "1") (pinfunction "1_1") (pintype "passive"))
    )
    (net (code "26") (name "CH1_STEP_L") (class "Default")
      (node (ref "INTERFACE") (pin "3") (pinfunction "3_3") (pintype "passive"))
      (node (ref "OK1") (pin "2") (pinfunction "C_2") (pintype "passive"))
    )
    (net (code "27") (name "CH2_A+") (class "Default")
      (node (ref "ENCODER2") (pin "3") (pinfunction "3_3") (pintype "passive"))
      (node (ref "IC3") (pin "5") (pinfunction "+IN_5") (pintype "input"))
    )
    (net (code "28") (name "CH2_A-") (class "Default")
      (node (ref "ENCODER2") (pin "7") (pinfunction "7_7") (pintype "passive"))
      (node (ref "IC3") (pin "4") (pinfunction "-IN_4") (pintype "input"))
      (node (ref "SJ2") (pin "2") (pinfunction "2_2") (pintype "passive"))
    )
    (net (code "29") (name "CH2_B+") (class "Default")
      (node (ref "ENCODER2") (pin "4") (pinfunction "4_4") (pintype "passive"))
      (node (ref "IC3") (pin "7") (pinfunction "+IN_7") (pintype "input"))
    )
    (net (code "30") (name "CH2_B-") (class "Default")
      (node (ref "ENCODER2") (pin "8") (pinfunction "8_8") (pintype "passive"))
      (node (ref "IC3") (pin "6") (pinfunction "-IN_6") (pintype "input"))
      (node (ref "SJ5") (pin "2") (pinfunction "2_2") (pintype "passive"))
    )
    (net (code "31") (name "CH2_CMD") (class "Default")
      (node (ref "IC6") (pin "13") (pinfunction "-IN_13") (pintype "input"))
      (node (ref "IC6") (pin "14") (pinfunction "OUT_14") (pintype "output"))
      (node (ref "OUTPUT") (pin "2") (pinfunction "2_2") (pintype "passive"))
    )
    (net (code "32") (name "CH2_DIR") (class "Default")
      (node (ref "IC9") (pin "32") (pinfunction "FLT15/RPB4/PMPA8/RB4_32") (pintype "bidirectional"))
      (node (ref "OK2") (pin "6") (pinfunction "VO_6") (pintype "passive"))
      (node (ref "R11") (pin "1") (pinfunction "1_1") (pintype "passive"))
    )
    (net (code "33") (name "CH2_DIR_H") (class "Default")
      (node (ref "INTERFACE") (pin "8") (pinfunction "8_8") (pintype "passive"))
      (node (ref "R13") (pin "1") (pinfunction "1_1") (pintype "passive"))
    )
    (net (code "34") (name "CH2_DIR_L") (class "Default")
      (node (ref "INTERFACE") (pin "9") (pinfunction "9_9") (pintype "passive"))
      (node (ref "OK2") (pin "3") (pinfunction "C_3") (pintype "passive"))
    )
    (net (code "35") (name "CH2_H") (class "Default")
      (node (ref "IC9") (pin "64") (pinfunction "TDO/PWM4H/PMPD4/RA10_64") (pintype "bidirectional"))
      (node (ref "R44") (pin "1") (pinfunction "1_1") (pintype "passive"))
    )
    (net (code "36") (name "CH2_I+") (class "Default")
      (node (ref "ENCODER2") (pin "5") (pinfunction "5_5") (pintype "passive"))
      (node (ref "IC3") (pin "9") (pinfunction "+IN_9") (pintype "input"))
    )
    (net (code "37") (name "CH2_I-") (class "Default")
      (node (ref "ENCODER2") (pin "9") (pinfunction "9_9") (pintype "passive"))
      (node (ref "IC3") (pin "8") (pinfunction "-IN_8") (pintype "input"))
      (node (ref "SJ8") (pin "2") (pinfunction "2_2") (pintype "passive"))
    )
    (net (code "38") (name "CH2_L") (class "Default")
      (node (ref "IC9") (pin "1") (pinfunction "TCK/RPA7/PWM10H/PWM4L/PMPD5/RA7_1") (pintype "bidirectional"))
      (node (ref "R51") (pin "1") (pinfunction "1_1") (pintype "passive"))
    )
    (net (code "39") (name "CH2_QE_A") (class "Default")
      (node (ref "IC3") (pin "2") (pinfunction "OUT_2") (pintype "open_collector"))
      (node (ref "IC9") (pin "23") (pinfunction "OA3IN+/AN8/CVD8/C3IN1+/C3IN3-/RPC2/FLT3/PMPA13/RC2_23") (pintype "input"))
      (node (ref "R19") (pin "1") (pinfunction "1_1") (pintype "passive"))
    )
    (net (code "40") (name "CH2_QE_B") (class "Default")
      (node (ref "IC3") (pin "1") (pinfunction "OUT_1") (pintype "open_collector"))
      (node (ref "IC9") (pin "22") (pinfunction "OA3IN-/AN7/CVD7/C3IN1-/C4IN1-/RPC1/PMPA7/RC1_22") (pintype "bidirectional"))
      (node (ref "R22") (pin "1") (pinfunction "1_1") (pintype "passive"))
    )
    (net (code "41") (name "CH2_QE_I") (class "Default")
      (node (ref "IC3") (pin "14") (pinfunction "OUT_14") (pintype "open_collector"))
      (node (ref "IC9") (pin "16") (pinfunction "PGEC3/OA1OUT/VREF+/AN3/C1IN4-/C4IN2-/RPB1/CTED1/PMPA6/RB1_16") (pintype "bidirectional"))
      (node (ref "R25") (pin "1") (pinfunction "1_1") (pintype "passive"))
    )
    (net (code "42") (name "CH2_STEP") (class "Default")
      (node (ref "IC9") (pin "29") (pinfunction "AN14/CVD14/RPE14/FLT7/PMPA1/PSPA1/RE14_29") (pintype "bidirectional"))
      (node (ref "OK2") (pin "7") (pinfunction "VO_7") (pintype "passive"))
      (node (ref "R7") (pin "1") (pinfunction "1_1") (pintype "passive"))
    )
    (net (code "43") (name "CH2_STEP_H") (class "Default")
      (node (ref "INTERFACE") (pin "6") (pinfunction "6_6") (pintype "passive"))
      (node (ref "R9") (pin "1") (pinfunction "1_1") (pintype "passive"))
    )
    (net (code "44") (name "CH2_STEP_L") (class "Default")
      (node (ref "INTERFACE") (pin "7") (pinfunction "7_7") (pintype "passive"))
      (node (ref "OK2") (pin "2") (pinfunction "C_2") (pintype "passive"))
    )
    (net (code "45") (name "CH3_A+") (class "Default")
      (node (ref "ENCODER3") (pin "3") (pinfunction "3_3") (pintype "passive"))
      (node (ref "IC4") (pin "5") (pinfunction "+IN_5") (pintype "input"))
    )
    (net (code "46") (name "CH3_A-") (class "Default")
      (node (ref "ENCODER3") (pin "7") (pinfunction "7_7") (pintype "passive"))
      (node (ref "IC4") (pin "4") (pinfunction "-IN_4") (pintype "input"))
      (node (ref "SJ3") (pin "2") (pinfunction "2_2") (pintype "passive"))
    )
    (net (code "47") (name "CH3_B+") (class "Default")
      (node (ref "ENCODER3") (pin "4") (pinfunction "4_4") (pintype "passive"))
      (node (ref "IC4") (pin "7") (pinfunction "+IN_7") (pintype "input"))
    )
    (net (code "48") (name "CH3_B-") (class "Default")
      (node (ref "ENCODER3") (pin "8") (pinfunction "8_8") (pintype "passive"))
      (node (ref "IC4") (pin "6") (pinfunction "-IN_6") (pintype "input"))
      (node (ref "SJ6") (pin "2") (pinfunction "2_2") (pintype "passive"))
    )
    (net (code "49") (name "CH3_CMD") (class "Default")
      (node (ref "IC7") (pin "13") (pinfunction "-IN_13") (pintype "input"))
      (node (ref "IC7") (pin "14") (pinfunction "OUT_14") (pintype "output"))
      (node (ref "OUTPUT") (pin "3") (pinfunction "3_3") (pintype "passive"))
    )
    (net (code "50") (name "CH3_DIR") (class "Default")
      (node (ref "IC9") (pin "24") (pinfunction "AN11/CVD11/C1IN2-/FLT4/PMPA12/RC11_24") (pintype "output"))
      (node (ref "OK3") (pin "6") (pinfunction "VO_6") (pintype "passive"))
      (node (ref "R16") (pin "1") (pinfunction "1_1") (pintype "passive"))
    )
    (net (code "51") (name "CH3_DIR_H") (class "Default")
      (node (ref "INTERFACE") (pin "12") (pinfunction "12_12") (pintype "passive"))
      (node (ref "R17") (pin "1") (pinfunction "1_1") (pintype "passive"))
    )
    (net (code "52") (name "CH3_DIR_L") (class "Default")
      (node (ref "INTERFACE") (pin "13") (pinfunction "13_13") (pintype "passive"))
      (node (ref "OK3") (pin "3") (pinfunction "C_3") (pintype "passive"))
    )
    (net (code "53") (name "CH3_H") (class "Default")
      (node (ref "IC9") (pin "62") (pinfunction "RPB12/PWM2H/PMPD2/RB12_62") (pintype "bidirectional"))
      (node (ref "R57") (pin "1") (pinfunction "1_1") (pintype "passive"))
    )
    (net (code "54") (name "CH3_I+") (class "Default")
      (node (ref "ENCODER3") (pin "5") (pinfunction "5_5") (pintype "passive"))
      (node (ref "IC4") (pin "9") (pinfunction "+IN_9") (pintype "input"))
    )
    (net (code "55") (name "CH3_I-") (class "Default")
      (node (ref "ENCODER3") (pin "9") (pinfunction "9_9") (pintype "passive"))
      (node (ref "IC4") (pin "8") (pinfunction "-IN_8") (pintype "input"))
      (node (ref "SJ9") (pin "2") (pinfunction "2_2") (pintype "passive"))
    )
    (net (code "56") (name "CH3_L") (class "Default")
      (node (ref "IC9") (pin "63") (pinfunction "RPB13/PWM8H/PWM2L/CTPLS/PMPD3/RB13_63") (pintype "bidirectional"))
      (node (ref "R64") (pin "1") (pinfunction "1_1") (pintype "passive"))
    )
    (net (code "57") (name "CH3_QE_A") (class "Default")
      (node (ref "IC4") (pin "2") (pinfunction "OUT_2") (pintype "open_collector"))
      (node (ref "IC9") (pin "13") (pinfunction "OA2OUT/ANO/C2IN4-/C4IN3-/RPA0/RA0_13") (pintype "bidirectional"))
      (node (ref "R20") (pin "1") (pinfunction "1_1") (pintype "passive"))
    )
    (net (code "58") (name "CH3_QE_B") (class "Default")
      (node (ref "IC4") (pin "1") (pinfunction "OUT_1") (pintype "open_collector"))
      (node (ref "IC9") (pin "14") (pinfunction "OA2IN+/AN1/C2IN1+/RPA1/RA1_14") (pintype "bidirectional"))
      (node (ref "R23") (pin "1") (pinfunction "1_1") (pintype "passive"))
    )
    (net (code "59") (name "CH3_QE_I") (class "Default")
      (node (ref "IC4") (pin "14") (pinfunction "OUT_14") (pintype "open_collector"))
      (node (ref "IC9") (pin "17") (pinfunction "PGEC1/OA1IN+/AN4/C1IN1+/C1IN3-/C2IN3-/RPB2/RB2_17") (pintype "bidirectional"))
      (node (ref "R26") (pin "1") (pinfunction "1_1") (pintype "passive"))
    )
    (net (code "60") (name "CH3_STEP") (class "Default")
      (node (ref "IC9") (pin "15") (pinfunction "PGED3/VREF-/OA2IN-/AN2/C2IN1-/RPB0/CTED2/RB0_15") (pintype "bidirectional"))
      (node (ref "OK3") (pin "7") (pinfunction "VO_7") (pintype "passive"))
      (node (ref "R14") (pin "1") (pinfunction "1_1") (pintype "passive"))
    )
    (net (code "61") (name "CH3_STEP_H") (class "Default")
      (node (ref "INTERFACE") (pin "10") (pinfunction "10_10") (pintype "passive"))
      (node (ref "R15") (pin "1") (pinfunction "1_1") (pintype "passive"))
    )
    (net (code "62") (name "CH3_STEP_L") (class "Default")
      (node (ref "INTERFACE") (pin "11") (pinfunction "11_11") (pintype "passive"))
      (node (ref "OK3") (pin "2") (pinfunction "C_2") (pintype "passive"))
    )
    (net (code "63") (name "DI1") (class "Default")
      (node (ref "IC9") (pin "4") (pinfunction "AN19/CVD19/RPG6/PMPA5/RG6_4") (pintype "bidirectional"))
      (node (ref "OK4") (pin "16") (pinfunction "C_16") (pintype "passive"))
      (node (ref "R73") (pin "1") (pinfunction "1_1") (pintype "passive"))
    )
    (net (code "64") (name "DI1_CON") (class "Default")
      (node (ref "INTERFACE") (pin "16") (pinfunction "16_16") (pintype "passive"))
      (node (ref "R74") (pin "1") (pinfunction "1_1") (pintype "passive"))
    )
    (net (code "65") (name "DI2") (class "Default")
      (node (ref "IC9") (pin "5") (pinfunction "AN18/CVD18/RPG7/PMPA4/RG7_5") (pintype "bidirectional"))
      (node (ref "OK4") (pin "14") (pinfunction "C_14") (pintype "passive"))
      (node (ref "R77") (pin "1") (pinfunction "1_1") (pintype "passive"))
    )
    (net (code "66") (name "DI2_CON") (class "Default")
      (node (ref "INTERFACE") (pin "17") (pinfunction "17_17") (pintype "passive"))
      (node (ref "R79") (pin "1") (pinfunction "1_1") (pintype "passive"))
    )
    (net (code "67") (name "DI3") (class "Default")
      (node (ref "IC9") (pin "6") (pinfunction "AN17/CVD17/RPG8/PMPA3/RG8_6") (pintype "bidirectional"))
      (node (ref "OK4") (pin "12") (pinfunction "C_12") (pintype "passive"))
      (node (ref "R82") (pin "1") (pinfunction "1_1") (pintype "passive"))
    )
    (net (code "68") (name "DI3_CON") (class "Default")
      (node (ref "INTERFACE") (pin "18") (pinfunction "18_18") (pintype "passive"))
      (node (ref "R84") (pin "1") (pinfunction "1_1") (pintype "passive"))
    )
    (net (code "69") (name "DI4") (class "Default")
      (node (ref "IC9") (pin "8") (pinfunction "AN16/CVD16/RPG9/PMPA2/RG9_8") (pintype "bidirectional"))
      (node (ref "OK4") (pin "10") (pinfunction "C_10") (pintype "passive"))
      (node (ref "R88") (pin "1") (pinfunction "1_1") (pintype "passive"))
    )
    (net (code "70") (name "DI4_CON") (class "Default")
      (node (ref "INTERFACE") (pin "19") (pinfunction "19_19") (pintype "passive"))
      (node (ref "R89") (pin "1") (pinfunction "1_1") (pintype "passive"))
    )
    (net (code "71") (name "DI_COM_CON") (class "Default")
      (node (ref "C42") (pin "2") (pinfunction "2_2") (pintype "passive"))
      (node (ref "C43") (pin "2") (pinfunction "2_2") (pintype "passive"))
      (node (ref "C44") (pin "2") (pinfunction "2_2") (pintype "passive"))
      (node (ref "C45") (pin "2") (pinfunction "2_2") (pintype "passive"))
      (node (ref "INTERFACE") (pin "20") (pinfunction "20_20") (pintype "passive"))
      (node (ref "OK4") (pin "2") (pinfunction "AC2_2") (pintype "passive"))
      (node (ref "OK4") (pin "4") (pinfunction "AC2_4") (pintype "passive"))
      (node (ref "OK4") (pin "6") (pinfunction "AC2_6") (pintype "passive"))
      (node (ref "OK4") (pin "8") (pinfunction "AC2_8") (pintype "passive"))
    )
    (net (code "72") (name "DO1") (class "Default")
      (node (ref "IC10") (pin "14") (pinfunction "I4_14") (pintype "input"))
      (node (ref "IC9") (pin "52") (pinfunction "TRD1/RPC8/PWM5H/PMPWR/PSPWR/RC8_52") (pintype "bidirectional"))
    )
    (net (code "73") (name "DO1_CON") (class "Default")
      (node (ref "IC10") (pin "16") (pinfunction "C4_16") (pintype "open_collector"))
      (node (ref "INTERFACE") (pin "21") (pinfunction "21_21") (pintype "passive"))
    )
    (net (code "74") (name "DO2") (class "Default")
      (node (ref "IC10") (pin "11") (pinfunction "I3_11") (pintype "input"))
      (node (ref "IC9") (pin "53") (pinfunction "TRD2/RPD5/PWM12H/PMPRD/PSPRD/RD5_53") (pintype "bidirectional"))
    )
    (net (code "75") (name "DO2_CON") (class "Default")
      (node (ref "IC10") (pin "9") (pinfunction "C3_9") (pintype "open_collector"))
      (node (ref "INTERFACE") (pin "22") (pinfunction "22_22") (pintype "passive"))
    )
    (net (code "76") (name "DO3") (class "Default")
      (node (ref "IC10") (pin "3") (pinfunction "I1_3") (pintype "input"))
      (node (ref "IC9") (pin "11") (pinfunction "AN10/CVD10/RPA12/RA12_11") (pintype "bidirectional"))
    )
    (net (code "77") (name "DO3_CON") (class "Default")
      (node (ref "IC10") (pin "1") (pinfunction "C1_1") (pintype "open_collector"))
      (node (ref "INTERFACE") (pin "23") (pinfunction "23_23") (pintype "passive"))
    )
    (net (code "78") (name "DO4") (class "Default")
      (node (ref "IC10") (pin "6") (pinfunction "I2_6") (pintype "input"))
      (node (ref "IC9") (pin "12") (pinfunction "AN9/CVD9/RPA11/USBOEN1/RA11_12") (pintype "bidirectional"))
    )
    (net (code "79") (name "DO4_CON") (class "Default")
      (node (ref "IC10") (pin "8") (pinfunction "C2_8") (pintype "open_collector"))
      (node (ref "INTERFACE") (pin "24") (pinfunction "24_24") (pintype "passive"))
    )
    (net (code "80") (name "DO_COM_CON") (class "Default")
      (node (ref "IC10") (pin "10") (pinfunction "E3_10") (pintype "open_collector"))
      (node (ref "IC10") (pin "15") (pinfunction "E4_15") (pintype "open_collector"))
      (node (ref "IC10") (pin "2") (pinfunction "E1_2") (pintype "open_collector"))
      (node (ref "IC10") (pin "7") (pinfunction "E2_7") (pintype "open_collector"))
      (node (ref "INTERFACE") (pin "25") (pinfunction "25_25") (pintype "passive"))
      (node (ref "SJ10") (pin "2") (pinfunction "2_2") (pintype "passive"))
    )
    (net (code "81") (name "GND") (class "Default")
      (node (ref "C10") (pin "2") (pinfunction "2_2") (pintype "passive"))
      (node (ref "C11") (pin "1") (pinfunction "1_1") (pintype "passive"))
      (node (ref "C12") (pin "1") (pinfunction "1_1") (pintype "passive"))
      (node (ref "C13") (pin "1") (pinfunction "1_1") (pintype "passive"))
      (node (ref "C14") (pin "1") (pinfunction "1_1") (pintype "passive"))
      (node (ref "C16") (pin "2") (pinfunction "2_2") (pintype "passive"))
      (node (ref "C18") (pin "2") (pinfunction "2_2") (pintype "passive"))
      (node (ref "C19") (pin "1") (pinfunction "1_1") (pintype "passive"))
      (node (ref "C21") (pin "2") (pinfunction "2_2") (pintype "passive"))
      (node (ref "C23") (pin "2") (pinfunction "2_2") (pintype "passive"))
      (node (ref "C24") (pin "1") (pinfunction "1_1") (pintype "passive"))
      (node (ref "C26") (pin "2") (pinfunction "2_2") (pintype "passive"))
      (node (ref "C28") (pin "2") (pinfunction "2_2") (pintype "passive"))
      (node (ref "C3") (pin "2") (pinfunction "2_2") (pintype "passive"))
      (node (ref "C31") (pin "2") (pinfunction "2_2") (pintype "passive"))
      (node (ref "C32") (pin "2") (pinfunction "2_2") (pintype "passive"))
      (node (ref "C33") (pin "-") (pinfunction "-_-") (pintype "passive"))
      (node (ref "C34") (pin "1") (pinfunction "1_1") (pintype "passive"))
      (node (ref "C35") (pin "1") (pinfunction "1_1") (pintype "passive"))
      (node (ref "C36") (pin "1") (pinfunction "1_1") (pintype "passive"))
      (node (ref "C37") (pin "2") (pinfunction "2_2") (pintype "passive"))
      (node (ref "C38") (pin "1") (pinfunction "1_1") (pintype "passive"))
      (node (ref "C39") (pin "1") (pinfunction "1_1") (pintype "passive"))
      (node (ref "C40") (pin "2") (pinfunction "2_2") (pintype "passive"))
      (node (ref "C41") (pin "1") (pinfunction "1_1") (pintype "passive"))
      (node (ref "C5") (pin "2") (pinfunction "2_2") (pintype "passive"))
      (node (ref "C7") (pin "1") (pinfunction "1_1") (pintype "passive"))
      (node (ref "C9") (pin "-") (pinfunction "-_-") (pintype "passive"))
      (node (ref "ENCODER1") (pin "1") (pinfunction "1_1") (pintype "passive"))
      (node (ref "ENCODER1") (pin "G1") (pinfunction "G1_G1") (pintype "passive"))
      (node (ref "ENCODER1") (pin "G2") (pinfunction "G2_G2") (pintype "passive"))
      (node (ref "ENCODER2") (pin "1") (pinfunction "1_1") (pintype "passive"))
      (node (ref "ENCODER2") (pin "G1") (pinfunction "G1_G1") (pintype "passive"))
      (node (ref "ENCODER2") (pin "G2") (pinfunction "G2_G2") (pintype "passive"))
      (node (ref "ENCODER3") (pin "1") (pinfunction "1_1") (pintype "passive"))
      (node (ref "ENCODER3") (pin "G1") (pinfunction "G1_G1") (pintype "passive"))
      (node (ref "ENCODER3") (pin "G2") (pinfunction "G2_G2") (pintype "passive"))
      (node (ref "IC1") (pin "2") (pinfunction "GND_2") (pintype "power_in"))
      (node (ref "IC1") (pin "3") (pinfunction "GND_3") (pintype "power_in"))
      (node (ref "IC1") (pin "5") (pinfunction "SET_5") (pintype "input"))
      (node (ref "IC1") (pin "6") (pinfunction "GND_6") (pintype "power_in"))
      (node (ref "IC1") (pin "7") (pinfunction "GND_7") (pintype "power_in"))
      (node (ref "IC10") (pin "12") (pinfunction "SUB3_12") (pintype "passive"))
      (node (ref "IC10") (pin "13") (pinfunction "SUB4_13") (pintype "passive"))
      (node (ref "IC10") (pin "4") (pinfunction "SUB1_4") (pintype "passive"))
      (node (ref "IC10") (pin "5") (pinfunction "SUB2_5") (pintype "passive"))
      (node (ref "IC2") (pin "12") (pinfunction "GND_12") (pintype "power_in"))
      (node (ref "IC3") (pin "12") (pinfunction "GND_12") (pintype "power_in"))
      (node (ref "IC4") (pin "12") (pinfunction "GND_12") (pintype "power_in"))
      (node (ref "IC8") (pin "1") (pinfunction "~{EN}_1") (pintype "input"))
      (node (ref "IC8") (pin "12") (pinfunction "FORCEON_12") (pintype "input"))
      (node (ref "IC8") (pin "14") (pinfunction "GND_14") (pintype "power_in"))
      (node (ref "IC9") (pin "20") (pinfunction "AVSS_20") (pintype "power_in"))
      (node (ref "IC9") (pin "25") (pinfunction "VSS_25") (pintype "power_in"))
      (node (ref "IC9") (pin "41") (pinfunction "VSS_41") (pintype "power_in"))
      (node (ref "IC9") (pin "56") (pinfunction "VSS_56") (pintype "power_in"))
      (node (ref "IC9") (pin "9") (pinfunction "VSS_9") (pintype "power_in"))
      (node (ref "IC9") (pin "EXP") (pinfunction "VSS_EXP") (pintype "power_in"))
      (node (ref "ICSP") (pin "3") (pinfunction "3_3") (pintype "passive"))
      (node (ref "INTERFACE") (pin "1") (pinfunction "1_1") (pintype "passive"))
      (node (ref "INTERFACE") (pin "G1") (pinfunction "G1_G1") (pintype "passive"))
      (node (ref "INTERFACE") (pin "G2") (pinfunction "G2_G2") (pintype "passive"))
      (node (ref "LED6") (pin "C") (pinfunction "C_C") (pintype "passive"))
      (node (ref "LED7") (pin "C") (pinfunction "C_C") (pintype "passive"))
      (node (ref "LED8") (pin "C") (pinfunction "C_C") (pintype "passive"))
      (node (ref "OK1") (pin "5") (pinfunction "GND_5") (pintype "power_in"))
      (node (ref "OK2") (pin "5") (pinfunction "GND_5") (pintype "power_in"))
      (node (ref "OK3") (pin "5") (pinfunction "GND_5") (pintype "power_in"))
      (node (ref "OK4") (pin "11") (pinfunction "E_11") (pintype "passive"))
      (node (ref "OK4") (pin "13") (pinfunction "E_13") (pintype "passive"))
      (node (ref "OK4") (pin "15") (pinfunction "E_15") (pintype "passive"))
      (node (ref "OK4") (pin "9") (pinfunction "E_9") (pintype "passive"))
      (node (ref "OUTPUT") (pin "6") (pinfunction "6_6") (pintype "passive"))
      (node (ref "OUTPUT") (pin "7") (pinfunction "7_7") (pintype "passive"))
      (node (ref "OUTPUT") (pin "8") (pinfunction "8_8") (pintype "passive"))
      (node (ref "OUTPUT") (pin "9") (pinfunction "9_9") (pintype "passive"))
      (node (ref "OUTPUT") (pin "G1") (pinfunction "G1_G1") (pintype "passive"))
      (node (ref "OUTPUT") (pin "G2") (pinfunction "G2_G2") (pintype "passive"))
      (node (ref "Q4") (pin "2") (pinfunction "E_2") (pintype "passive"))
      (node (ref "R2") (pin "2") (pinfunction "2_2") (pintype "passive"))
      (node (ref "R28") (pin "1") (pinfunction "1_1") (pintype "passive"))
      (node (ref "R29") (pin "2") (pinfunction "2_2") (pintype "passive"))
      (node (ref "R3") (pin "2") (pinfunction "2_2") (pintype "passive"))
      (node (ref "R33") (pin "1") (pinfunction "1_1") (pintype "passive"))
      (node (ref "R4") (pin "2") (pinfunction "2_2") (pintype "passive"))
      (node (ref "R41") (pin "1") (pinfunction "1_1") (pintype "passive"))
      (node (ref "R42") (pin "2") (pinfunction "2_2") (pintype "passive"))
      (node (ref "R46") (pin "1") (pinfunction "1_1") (pintype "passive"))
      (node (ref "R5") (pin "2") (pinfunction "2_2") (pintype "passive"))
      (node (ref "R54") (pin "1") (pinfunction "1_1") (pintype "passive"))
      (node (ref "R55") (pin "2") (pinfunction "2_2") (pintype "passive"))
      (node (ref "R59") (pin "1") (pinfunction "1_1") (pintype "passive"))
      (node (ref "R67") (pin "1") (pinfunction "1_1") (pintype "passive"))
      (node (ref "RS-232") (pin "5") (pinfunction "5_5") (pintype "passive"))
      (node (ref "RS-232") (pin "G1") (pinfunction "G1_G1") (pintype "passive"))
      (node (ref "RS-232") (pin "G2") (pinfunction "G2_G2") (pintype "passive"))
      (node (ref "SJ10") (pin "1") (pinfunction "1_1") (pintype "passive"))
      (node (ref "U1") (pin "6") (pinfunction "-OUT_6") (pintype "output"))
      (node (ref "U2") (pin "16") (pinfunction "COM_16") (pintype "passive"))
      (node (ref "U2") (pin "9") (pinfunction "COM_9") (pintype "passive"))
    )
    (net (code "82") (name "LED_ERROR") (class "Default")
      (node (ref "IC9") (pin "60") (pinfunction "RPB10/PWM3H/PMPD0/RB10_60") (pintype "bidirectional"))
      (node (ref "R70") (pin "1") (pinfunction "1_1") (pintype "passive"))
    )
    (net (code "83") (name "LED_READY") (class "Default")
      (node (ref "IC9") (pin "58") (pinfunction "RPF0/PWM11H/RF0_58") (pintype "bidirectional"))
      (node (ref "R68") (pin "1") (pinfunction "1_1") (pintype "passive"))
    )
    (net (code "84") (name "LED_STATE") (class "Default")
      (node (ref "IC9") (pin "59") (pinfunction "RPF1/PWM11L/RF1_59") (pintype "bidirectional"))
      (node (ref "R69") (pin "1") (pinfunction "1_1") (pintype "passive"))
    )
    (net (code "85") (name "Net-(C15-Pad2)") (class "Default")
      (node (ref "C15") (pin "2") (pinfunction "2_2") (pintype "passive"))
      (node (ref "R31") (pin "2") (pinfunction "2_2") (pintype "passive"))
      (node (ref "R32") (pin "1") (pinfunction "1_1") (pintype "passive"))
    )
    (net (code "86") (name "Net-(C17-Pad1)") (class "Default")
      (node (ref "C17") (pin "1") (pinfunction "1_1") (pintype "passive"))
      (node (ref "R38") (pin "2") (pinfunction "2_2") (pintype "passive"))
      (node (ref "R39") (pin "1") (pinfunction "1_1") (pintype "passive"))
    )
    (net (code "87") (name "Net-(C20-Pad2)") (class "Default")
      (node (ref "C20") (pin "2") (pinfunction "2_2") (pintype "passive"))
      (node (ref "R44") (pin "2") (pinfunction "2_2") (pintype "passive"))
      (node (ref "R45") (pin "1") (pinfunction "1_1") (pintype "passive"))
    )
    (net (code "88") (name "Net-(C22-Pad1)") (class "Default")
      (node (ref "C22") (pin "1") (pinfunction "1_1") (pintype "passive"))
      (node (ref "R51") (pin "2") (pinfunction "2_2") (pintype "passive"))
      (node (ref "R52") (pin "1") (pinfunction "1_1") (pintype "passive"))
    )
    (net (code "89") (name "Net-(C25-Pad2)") (class "Default")
      (node (ref "C25") (pin "2") (pinfunction "2_2") (pintype "passive"))
      (node (ref "R57") (pin "2") (pinfunction "2_2") (pintype "passive"))
      (node (ref "R58") (pin "1") (pinfunction "1_1") (pintype "passive"))
    )
    (net (code "90") (name "Net-(C27-Pad1)") (class "Default")
      (node (ref "C27") (pin "1") (pinfunction "1_1") (pintype "passive"))
      (node (ref "R64") (pin "2") (pinfunction "2_2") (pintype "passive"))
      (node (ref "R65") (pin "1") (pinfunction "1_1") (pintype "passive"))
    )
    (net (code "91") (name "Net-(C34-Pad2)") (class "Default")
      (node (ref "C34") (pin "2") (pinfunction "2_2") (pintype "passive"))
      (node (ref "R71") (pin "1") (pinfunction "1_1") (pintype "passive"))
      (node (ref "R72") (pin "1") (pinfunction "1_1") (pintype "passive"))
    )
    (net (code "92") (name "Net-(D1-A)") (class "Default")
      (node (ref "D1") (pin "1") (pinfunction "A_1") (pintype "passive"))
      (node (ref "K1") (pin "8") (pinfunction "-_8") (pintype "passive"))
      (node (ref "Q4") (pin "3") (pinfunction "C_3") (pintype "passive"))
    )
    (net (code "93") (name "Net-(IC5A-+IN)") (class "Default")
      (node (ref "C14") (pin "2") (pinfunction "2_2") (pintype "passive"))
      (node (ref "IC5") (pin "3") (pinfunction "+IN_3") (pintype "input"))
      (node (ref "R32") (pin "2") (pinfunction "2_2") (pintype "passive"))
    )
    (net (code "94") (name "Net-(IC5A--IN)") (class "Default")
      (node (ref "IC5") (pin "2") (pinfunction "-IN_2") (pintype "input"))
      (node (ref "R29") (pin "1") (pinfunction "1_1") (pintype "passive"))
      (node (ref "R30") (pin "2") (pinfunction "2_2") (pintype "passive"))
    )
    (net (code "95") (name "Net-(IC5A-OUT)") (class "Default")
      (node (ref "C15") (pin "1") (pinfunction "1_1") (pintype "passive"))
      (node (ref "IC5") (pin "1") (pinfunction "OUT_1") (pintype "output"))
      (node (ref "R30") (pin "1") (pinfunction "1_1") (pintype "passive"))
      (node (ref "R34") (pin "2") (pinfunction "2_2") (pintype "passive"))
    )
    (net (code "96") (name "Net-(IC5B-+IN)") (class "Default")
      (node (ref "C18") (pin "1") (pinfunction "1_1") (pintype "passive"))
      (node (ref "IC5") (pin "5") (pinfunction "+IN_5") (pintype "input"))
      (node (ref "R39") (pin "2") (pinfunction "2_2") (pintype "passive"))
    )
    (net (code "97") (name "Net-(IC5B--IN)") (class "Default")
      (node (ref "IC5") (pin "6") (pinfunction "-IN_6") (pintype "input"))
      (node (ref "R40") (pin "1") (pinfunction "1_1") (pintype "passive"))
      (node (ref "R41") (pin "2") (pinfunction "2_2") (pintype "passive"))
    )
    (net (code "98") (name "Net-(IC5B-OUT)") (class "Default")
      (node (ref "C17") (pin "2") (pinfunction "2_2") (pintype "passive"))
      (node (ref "IC5") (pin "7") (pinfunction "OUT_7") (pintype "output"))
      (node (ref "R36") (pin "2") (pinfunction "2_2") (pintype "passive"))
      (node (ref "R40") (pin "2") (pinfunction "2_2") (pintype "passive"))
    )
    (net (code "99") (name "Net-(IC5C-+IN)") (class "Default")
      (node (ref "IC5") (pin "10") (pinfunction "+IN_10") (pintype "input"))
      (node (ref "R33") (pin "2") (pinfunction "2_2") (pintype "passive"))
      (node (ref "R34") (pin "1") (pinfunction "1_1") (pintype "passive"))
    )
    (net (code "100") (name "Net-(IC5C--IN)") (class "Default")
      (node (ref "IC5") (pin "9") (pinfunction "-IN_9") (pintype "input"))
      (node (ref "R36") (pin "1") (pinfunction "1_1") (pintype "passive"))
      (node (ref "R37") (pin "1") (pinfunction "1_1") (pintype "passive"))
    )
    (net (code "101") (name "Net-(IC5C-OUT)") (class "Default")
      (node (ref "IC5") (pin "8") (pinfunction "OUT_8") (pintype "output"))
      (node (ref "R35") (pin "1") (pinfunction "1_1") (pintype "passive"))
      (node (ref "R37") (pin "2") (pinfunction "2_2") (pintype "passive"))
    )
    (net (code "102") (name "Net-(IC5D-+IN)") (class "Default")
      (node (ref "C16") (pin "1") (pinfunction "1_1") (pintype "passive"))
      (node (ref "IC5") (pin "12") (pinfunction "+IN_12") (pintype "input"))
      (node (ref "R35") (pin "2") (pinfunction "2_2") (pintype "passive"))
    )
    (net (code "103") (name "Net-(IC6A-+IN)") (class "Default")
      (node (ref "C19") (pin "2") (pinfunction "2_2") (pintype "passive"))
      (node (ref "IC6") (pin "3") (pinfunction "+IN_3") (pintype "input"))
      (node (ref "R45") (pin "2") (pinfunction "2_2") (pintype "passive"))
    )
    (net (code "104") (name "Net-(IC6A--IN)") (class "Default")
      (node (ref "IC6") (pin "2") (pinfunction "-IN_2") (pintype "input"))
      (node (ref "R42") (pin "1") (pinfunction "1_1") (pintype "passive"))
      (node (ref "R43") (pin "2") (pinfunction "2_2") (pintype "passive"))
    )
    (net (code "105") (name "Net-(IC6A-OUT)") (class "Default")
      (node (ref "C20") (pin "1") (pinfunction "1_1") (pintype "passive"))
      (node (ref "IC6") (pin "1") (pinfunction "OUT_1") (pintype "output"))
      (node (ref "R43") (pin "1") (pinfunction "1_1") (pintype "passive"))
      (node (ref "R47") (pin "2") (pinfunction "2_2") (pintype "passive"))
    )
    (net (code "106") (name "Net-(IC6B-+IN)") (class "Default")
      (node (ref "C23") (pin "1") (pinfunction "1_1") (pintype "passive"))
      (node (ref "IC6") (pin "5") (pinfunction "+IN_5") (pintype "input"))
      (node (ref "R52") (pin "2") (pinfunction "2_2") (pintype "passive"))
    )
    (net (code "107") (name "Net-(IC6B--IN)") (class "Default")
      (node (ref "IC6") (pin "6") (pinfunction "-IN_6") (pintype "input"))
      (node (ref "R53") (pin "1") (pinfunction "1_1") (pintype "passive"))
      (node (ref "R54") (pin "2") (pinfunction "2_2") (pintype "passive"))
    )
    (net (code "108") (name "Net-(IC6B-OUT)") (class "Default")
      (node (ref "C22") (pin "2") (pinfunction "2_2") (pintype "passive"))
      (node (ref "IC6") (pin "7") (pinfunction "OUT_7") (pintype "output"))
      (node (ref "R49") (pin "2") (pinfunction "2_2") (pintype "passive"))
      (node (ref "R53") (pin "2") (pinfunction "2_2") (pintype "passive"))
    )
    (net (code "109") (name "Net-(IC6C-+IN)") (class "Default")
      (node (ref "IC6") (pin "10") (pinfunction "+IN_10") (pintype "input"))
      (node (ref "R46") (pin "2") (pinfunction "2_2") (pintype "passive"))
      (node (ref "R47") (pin "1") (pinfunction "1_1") (pintype "passive"))
    )
    (net (code "110") (name "Net-(IC6C--IN)") (class "Default")
      (node (ref "IC6") (pin "9") (pinfunction "-IN_9") (pintype "input"))
      (node (ref "R49") (pin "1") (pinfunction "1_1") (pintype "passive"))
      (node (ref "R50") (pin "1") (pinfunction "1_1") (pintype "passive"))
    )
    (net (code "111") (name "Net-(IC6C-OUT)") (class "Default")
      (node (ref "IC6") (pin "8") (pinfunction "OUT_8") (pintype "output"))
      (node (ref "R48") (pin "1") (pinfunction "1_1") (pintype "passive"))
      (node (ref "R50") (pin "2") (pinfunction "2_2") (pintype "passive"))
    )
    (net (code "112") (name "Net-(IC6D-+IN)") (class "Default")
      (node (ref "C21") (pin "1") (pinfunction "1_1") (pintype "passive"))
      (node (ref "IC6") (pin "12") (pinfunction "+IN_12") (pintype "input"))
      (node (ref "R48") (pin "2") (pinfunction "2_2") (pintype "passive"))
    )
    (net (code "113") (name "Net-(IC7A-+IN)") (class "Default")
      (node (ref "C24") (pin "2") (pinfunction "2_2") (pintype "passive"))
      (node (ref "IC7") (pin "3") (pinfunction "+IN_3") (pintype "input"))
      (node (ref "R58") (pin "2") (pinfunction "2_2") (pintype "passive"))
    )
    (net (code "114") (name "Net-(IC7A--IN)") (class "Default")
      (node (ref "IC7") (pin "2") (pinfunction "-IN_2") (pintype "input"))
      (node (ref "R55") (pin "1") (pinfunction "1_1") (pintype "passive"))
      (node (ref "R56") (pin "2") (pinfunction "2_2") (pintype "passive"))
    )
    (net (code "115") (name "Net-(IC7A-OUT)") (class "Default")
      (node (ref "C25") (pin "1") (pinfunction "1_1") (pintype "passive"))
      (node (ref "IC7") (pin "1") (pinfunction "OUT_1") (pintype "output"))
      (node (ref "R56") (pin "1") (pinfunction "1_1") (pintype "passive"))
      (node (ref "R60") (pin "2") (pinfunction "2_2") (pintype "passive"))
    )
    (net (code "116") (name "Net-(IC7B-+IN)") (class "Default")
      (node (ref "C28") (pin "1") (pinfunction "1_1") (pintype "passive"))
      (node (ref "IC7") (pin "5") (pinfunction "+IN_5") (pintype "input"))
      (node (ref "R65") (pin "2") (pinfunction "2_2") (pintype "passive"))
    )
    (net (code "117") (name "Net-(IC7B--IN)") (class "Default")
      (node (ref "IC7") (pin "6") (pinfunction "-IN_6") (pintype "input"))
      (node (ref "R66") (pin "1") (pinfunction "1_1") (pintype "passive"))
      (node (ref "R67") (pin "2") (pinfunction "2_2") (pintype "passive"))
    )
    (net (code "118") (name "Net-(IC7B-OUT)") (class "Default")
      (node (ref "C27") (pin "2") (pinfunction "2_2") (pintype "passive"))
      (node (ref "IC7") (pin "7") (pinfunction "OUT_7") (pintype "output"))
      (node (ref "R62") (pin "2") (pinfunction "2_2") (pintype "passive"))
      (node (ref "R66") (pin "2") (pinfunction "2_2") (pintype "passive"))
    )
    (net (code "119") (name "Net-(IC7C-+IN)") (class "Default")
      (node (ref "IC7") (pin "10") (pinfunction "+IN_10") (pintype "input"))
      (node (ref "R59") (pin "2") (pinfunction "2_2") (pintype "passive"))
      (node (ref "R60") (pin "1") (pinfunction "1_1") (pintype "passive"))
    )
    (net (code "120") (name "Net-(IC7C--IN)") (class "Default")
      (node (ref "IC7") (pin "9") (pinfunction "-IN_9") (pintype "input"))
      (node (ref "R62") (pin "1") (pinfunction "1_1") (pintype "passive"))
      (node (ref "R63") (pin "1") (pinfunction "1_1") (pintype "passive"))
    )
    (net (code "121") (name "Net-(IC7C-OUT)") (class "Default")
      (node (ref "IC7") (pin "8") (pinfunction "OUT_8") (pintype "output"))
      (node (ref "R61") (pin "1") (pinfunction "1_1") (pintype "passive"))
      (node (ref "R63") (pin "2") (pinfunction "2_2") (pintype "passive"))
    )
    (net (code "122") (name "Net-(IC7D-+IN)") (class "Default")
      (node (ref "C26") (pin "1") (pinfunction "1_1") (pintype "passive"))
      (node (ref "IC7") (pin "12") (pinfunction "+IN_12") (pintype "input"))
      (node (ref "R61") (pin "2") (pinfunction "2_2") (pintype "passive"))
    )
    (net (code "123") (name "Net-(IC8A-C1+)") (class "Default")
      (node (ref "C30") (pin "1") (pinfunction "1_1") (pintype "passive"))
      (node (ref "IC8") (pin "2") (pinfunction "C1+_2") (pintype "passive"))
    )
    (net (code "124") (name "Net-(IC8A-C1-)") (class "Default")
      (node (ref "C30") (pin "2") (pinfunction "2_2") (pintype "passive"))
      (node (ref "IC8") (pin "4") (pinfunction "C1-_4") (pintype "passive"))
    )
    (net (code "125") (name "Net-(IC8A-C2+)") (class "Default")
      (node (ref "C29") (pin "1") (pinfunction "1_1") (pintype "passive"))
      (node (ref "IC8") (pin "5") (pinfunction "C2+_5") (pintype "passive"))
    )
    (net (code "126") (name "Net-(IC8A-C2-)") (class "Default")
      (node (ref "C29") (pin "2") (pinfunction "2_2") (pintype "passive"))
      (node (ref "IC8") (pin "6") (pinfunction "C2-_6") (pintype "passive"))
    )
    (net (code "127") (name "Net-(IC8A-V+)") (class "Default")
      (node (ref "C31") (pin "1") (pinfunction "1_1") (pintype "passive"))
      (node (ref "IC8") (pin "3") (pinfunction "V+_3") (pintype "passive"))
    )
    (net (code "128") (name "Net-(IC8A-V-)") (class "Default")
      (node (ref "C32") (pin "1") (pinfunction "1_1") (pintype "passive"))
      (node (ref "IC8") (pin "7") (pinfunction "V-_7") (pintype "passive"))
    )
    (net (code "129") (name "Net-(L1-2)") (class "Default")
      (node (ref "L1") (pin "B") (pinfunction "2_B") (pintype "passive"))
      (node (ref "U1") (pin "1") (pinfunction "+IN_1") (pintype "input"))
    )
    (net (code "130") (name "Net-(LED1-PadC)") (class "Default")
      (node (ref "LED1") (pin "C") (pinfunction "C_C") (pintype "passive"))
      (node (ref "R1") (pin "1") (pinfunction "1_1") (pintype "passive"))
    )
    (net (code "131") (name "Net-(LED2-PadC)") (class "Default")
      (node (ref "LED2") (pin "C") (pinfunction "C_C") (pintype "passive"))
      (node (ref "R2") (pin "1") (pinfunction "1_1") (pintype "passive"))
    )
    (net (code "132") (name "Net-(LED3-PadA)") (class "Default")
      (node (ref "LED3") (pin "A") (pinfunction "A_A") (pintype "passive"))
      (node (ref "R3") (pin "1") (pinfunction "1_1") (pintype "passive"))
    )
    (net (code "133") (name "Net-(LED4-PadC)") (class "Default")
      (node (ref "LED4") (pin "C") (pinfunction "C_C") (pintype "passive"))
      (node (ref "R4") (pin "1") (pinfunction "1_1") (pintype "passive"))
    )
    (net (code "134") (name "Net-(LED5-PadC)") (class "Default")
      (node (ref "LED5") (pin "C") (pinfunction "C_C") (pintype "passive"))
      (node (ref "R5") (pin "1") (pinfunction "1_1") (pintype "passive"))
    )
    (net (code "135") (name "Net-(LED6-PadA)") (class "Default")
      (node (ref "LED6") (pin "A") (pinfunction "A_A") (pintype "passive"))
      (node (ref "R68") (pin "2") (pinfunction "2_2") (pintype "passive"))
    )
    (net (code "136") (name "Net-(LED7-PadA)") (class "Default")
      (node (ref "LED7") (pin "A") (pinfunction "A_A") (pintype "passive"))
      (node (ref "R69") (pin "2") (pinfunction "2_2") (pintype "passive"))
    )
    (net (code "137") (name "Net-(LED8-PadA)") (class "Default")
      (node (ref "LED8") (pin "A") (pinfunction "A_A") (pintype "passive"))
      (node (ref "R70") (pin "2") (pinfunction "2_2") (pintype "passive"))
    )
    (net (code "138") (name "Net-(OK1A-A)") (class "Default")
      (node (ref "OK1") (pin "1") (pinfunction "A_1") (pintype "passive"))
      (node (ref "R8") (pin "2") (pinfunction "2_2") (pintype "passive"))
    )
    (net (code "139") (name "Net-(OK1B-A)") (class "Default")
      (node (ref "OK1") (pin "4") (pinfunction "A_4") (pintype "passive"))
      (node (ref "R12") (pin "2") (pinfunction "2_2") (pintype "passive"))
    )
    (net (code "140") (name "Net-(OK2A-A)") (class "Default")
      (node (ref "OK2") (pin "1") (pinfunction "A_1") (pintype "passive"))
      (node (ref "R9") (pin "2") (pinfunction "2_2") (pintype "passive"))
    )
    (net (code "141") (name "Net-(OK2B-A)") (class "Default")
      (node (ref "OK2") (pin "4") (pinfunction "A_4") (pintype "passive"))
      (node (ref "R13") (pin "2") (pinfunction "2_2") (pintype "passive"))
    )
    (net (code "142") (name "Net-(OK3A-A)") (class "Default")
      (node (ref "OK3") (pin "1") (pinfunction "A_1") (pintype "passive"))
      (node (ref "R15") (pin "2") (pinfunction "2_2") (pintype "passive"))
    )
    (net (code "143") (name "Net-(OK3B-A)") (class "Default")
      (node (ref "OK3") (pin "4") (pinfunction "A_4") (pintype "passive"))
      (node (ref "R17") (pin "2") (pinfunction "2_2") (pintype "passive"))
    )
    (net (code "144") (name "Net-(OK4A-AC1)") (class "Default")
      (node (ref "C42") (pin "1") (pinfunction "1_1") (pintype "passive"))
      (node (ref "OK4") (pin "1") (pinfunction "AC1_1") (pintype "passive"))
      (node (ref "R74") (pin "2") (pinfunction "2_2") (pintype "passive"))
    )
    (net (code "145") (name "Net-(OK4B-AC1)") (class "Default")
      (node (ref "C43") (pin "1") (pinfunction "1_1") (pintype "passive"))
      (node (ref "OK4") (pin "3") (pinfunction "AC1_3") (pintype "passive"))
      (node (ref "R79") (pin "2") (pinfunction "2_2") (pintype "passive"))
    )
    (net (code "146") (name "Net-(OK4C-AC1)") (class "Default")
      (node (ref "C44") (pin "1") (pinfunction "1_1") (pintype "passive"))
      (node (ref "OK4") (pin "5") (pinfunction "AC1_5") (pintype "passive"))
      (node (ref "R84") (pin "2") (pinfunction "2_2") (pintype "passive"))
    )
    (net (code "147") (name "Net-(OK4D-AC1)") (class "Default")
      (node (ref "C45") (pin "1") (pinfunction "1_1") (pintype "passive"))
      (node (ref "OK4") (pin "7") (pinfunction "AC1_7") (pintype "passive"))
      (node (ref "R89") (pin "2") (pinfunction "2_2") (pintype "passive"))
    )
    (net (code "148") (name "Net-(Q4-B)") (class "Default")
      (node (ref "Q4") (pin "1") (pinfunction "B_1") (pintype "passive"))
      (node (ref "R81") (pin "2") (pinfunction "2_2") (pintype "passive"))
    )
    (net (code "149") (name "OSC1I") (class "Default")
      (node (ref "C38") (pin "2") (pinfunction "2_2") (pintype "passive"))
      (node (ref "IC9") (pin "39") (pinfunction "OSCI/CLKI/AN49/CVD49/RPC12/RC12_39") (pintype "bidirectional"))
      (node (ref "Q1") (pin "2") (pinfunction "2_2") (pintype "passive"))
    )
    (net (code "150") (name "OSC1O") (class "Default")
      (node (ref "C41") (pin "2") (pinfunction "2_2") (pintype "passive"))
      (node (ref "IC9") (pin "40") (pinfunction "OSCO/CLKO/RPC15/RC15_40") (pintype "bidirectional"))
      (node (ref "Q1") (pin "1") (pinfunction "1_1") (pintype "passive"))
    )
    (net (code "151") (name "PGEC") (class "Default")
      (node (ref "IC9") (pin "44") (pinfunction "PGEC2/RPB6/SCK2/PMPA15/RB6_44") (pintype "bidirectional"))
      (node (ref "ICSP") (pin "5") (pinfunction "5_5") (pintype "passive"))
    )
    (net (code "152") (name "PGED") (class "Default")
      (node (ref "IC9") (pin "43") (pinfunction "PGED2/RPB5/USBID1/RB5_43") (pintype "bidirectional"))
      (node (ref "ICSP") (pin "4") (pinfunction "4_4") (pintype "passive"))
    )
    (net (code "153") (name "RO1") (class "Default")
      (node (ref "IC9") (pin "61") (pinfunction "RPB11/PWM9H/PWM3L/PMPD1/RB11_61") (pintype "bidirectional"))
      (node (ref "R81") (pin "1") (pinfunction "1_1") (pintype "passive"))
    )
    (net (code "154") (name "RO1_COM_CON") (class "Default")
      (node (ref "K1") (pin "3") (pinfunction "P_3") (pintype "passive"))
      (node (ref "READY") (pin "2") (pinfunction "KL_2") (pintype "passive"))
    )
    (net (code "155") (name "RO1_NC_CON") (class "Default")
      (node (ref "K1") (pin "2") (pinfunction "O_2") (pintype "passive"))
      (node (ref "READY") (pin "3") (pinfunction "KL_3") (pintype "passive"))
    )
    (net (code "156") (name "RO1_NO_CON") (class "Default")
      (node (ref "K1") (pin "4") (pinfunction "S_4") (pintype "passive"))
      (node (ref "READY") (pin "1") (pinfunction "KL_1") (pintype "passive"))
    )
    (net (code "157") (name "RS232_RX") (class "Default")
      (node (ref "IC8") (pin "8") (pinfunction "R1IN_8") (pintype "input"))
      (node (ref "RS-232") (pin "2") (pinfunction "2_2") (pintype "passive"))
    )
    (net (code "158") (name "RS232_TX") (class "Default")
      (node (ref "IC8") (pin "13") (pinfunction "T1OUT_13") (pintype "output"))
      (node (ref "RS-232") (pin "3") (pinfunction "3_3") (pintype "passive"))
    )
    (net (code "159") (name "UART_RX") (class "Default")
      (node (ref "IC8") (pin "9") (pinfunction "R1OUT_9") (pintype "output"))
      (node (ref "IC9") (pin "55") (pinfunction "RPC9/PWM11H/PWM5L/RC9_55") (pintype "bidirectional"))
    )
    (net (code "160") (name "UART_TX") (class "Default")
      (node (ref "IC8") (pin "11") (pinfunction "T1IN_11") (pintype "input"))
      (node (ref "IC9") (pin "54") (pinfunction "TRD3/RPD6/PWM12L/RD6_54") (pintype "bidirectional"))
    )
    (net (code "161") (name "unconnected-(IC8A-~{INVALID}-Pad10)") (class "Default")
      (node (ref "IC8") (pin "10") (pinfunction "~{INVALID}_10") (pintype "input"))
    )
    (net (code "162") (name "unconnected-(IC9-AN12{slash}CVD12{slash}C2IN2-{slash}C5IN2-{slash}FLT5{slash}PMPA11{slash}RE12-Pad27)") (class "Default")
      (node (ref "IC9") (pin "27") (pinfunction "AN12/CVD12/C2IN2-/C5IN2-/FLT5/PMPA11/RE12_27") (pintype "input"))
    )
    (net (code "163") (name "unconnected-(IC9-AN13{slash}CVD13{slash}C3IN2-{slash}FLT6{slash}PMPA10{slash}RE13-Pad28)") (class "Default")
      (node (ref "IC9") (pin "28") (pinfunction "AN13/CVD13/C3IN2-/FLT6/PMPA10/RE13_28") (pintype "input"))
    )
    (net (code "164") (name "unconnected-(IC9-D+-Pad37)") (class "Default")
      (node (ref "IC9") (pin "37") (pinfunction "D+_37") (pintype "bidirectional"))
    )
    (net (code "165") (name "unconnected-(IC9-D--Pad36)") (class "Default")
      (node (ref "IC9") (pin "36") (pinfunction "D-_36") (pintype "bidirectional"))
    )
    (net (code "166") (name "unconnected-(IC9-DAC2{slash}AN48{slash}CVD48{slash}RPC10{slash}PMPA14{slash}PSPCS{slash}RC10-Pad45)") (class "Default")
      (node (ref "IC9") (pin "45") (pinfunction "DAC2/AN48/CVD48/RPC10/PMPA14/PSPCS/RC10_45") (pintype "bidirectional"))
    )
    (net (code "167") (name "unconnected-(IC9-OA5OUT{slash}AN25{slash}CVD25{slash}C5IN4-{slash}RPB7{slash}SCK1{slash}INT0{slash}RB7-Pad46)") (class "Default")
      (node (ref "IC9") (pin "46") (pinfunction "OA5OUT/AN25/CVD25/C5IN4-/RPB7/SCK1/INT0/RB7_46") (pintype "bidirectional"))
    )
    (net (code "168") (name "unconnected-(IC9-RD8-Pad42)") (class "Default")
      (node (ref "IC9") (pin "42") (pinfunction "RD8_42") (pintype "bidirectional"))
    )
    (net (code "169") (name "unconnected-(IC9-SOSCI{slash}RPC13{slash}RC13-Pad47)") (class "Default")
      (node (ref "IC9") (pin "47") (pinfunction "SOSCI/RPC13/RC13_47") (pintype "bidirectional"))
    )
    (net (code "170") (name "unconnected-(IC9-SOSCO{slash}RPB8{slash}RB8-Pad48)") (class "Default")
      (node (ref "IC9") (pin "48") (pinfunction "SOSCO/RPB8/RB8_48") (pintype "bidirectional"))
    )
    (net (code "171") (name "unconnected-(IC9-TMS{slash}OA5IN-{slash}AN27{slash}CVD27{slash}C5IN1-{slash}RPB9{slash}RB9-Pad49)") (class "Default")
      (node (ref "IC9") (pin "49") (pinfunction "TMS/OA5IN-/AN27/CVD27/C5IN1-/RPB9/RB9_49") (pintype "bidirectional"))
    )
    (net (code "172") (name "unconnected-(IC9-TRCLK{slash}RPC6{slash}PWM6H{slash}RC6-Pad50)") (class "Default")
      (node (ref "IC9") (pin "50") (pinfunction "TRCLK/RPC6/PWM6H/RC6_50") (pintype "bidirectional"))
    )
    (net (code "173") (name "unconnected-(IC9-TRD0{slash}RPC7{slash}PWM12H{slash}PWM6L{slash}RC7-Pad51)") (class "Default")
      (node (ref "IC9") (pin "51") (pinfunction "TRD0/RPC7/PWM12H/PWM6L/RC7_51") (pintype "bidirectional"))
    )
    (net (code "174") (name "unconnected-(IC9-VBUS-Pad34)") (class "Default")
      (node (ref "IC9") (pin "34") (pinfunction "VBUS_34") (pintype "bidirectional"))
    )
    (net (code "175") (name "unconnected-(OUTPUT-Pad4)") (class "Default")
      (node (ref "OUTPUT") (pin "4") (pinfunction "4_4") (pintype "passive"))
    )
    (net (code "176") (name "unconnected-(OUTPUT-Pad5)") (class "Default")
      (node (ref "OUTPUT") (pin "5") (pinfunction "5_5") (pintype "passive"))
    )
    (net (code "177") (name "unconnected-(RS-232-Pad1)") (class "Default")
      (node (ref "RS-232") (pin "1") (pinfunction "1_1") (pintype "passive"))
    )
    (net (code "178") (name "unconnected-(RS-232-Pad4)") (class "Default")
      (node (ref "RS-232") (pin "4") (pinfunction "4_4") (pintype "passive"))
    )
    (net (code "179") (name "unconnected-(RS-232-Pad6)") (class "Default")
      (node (ref "RS-232") (pin "6") (pinfunction "6_6") (pintype "passive"))
    )
    (net (code "180") (name "unconnected-(RS-232-Pad7)") (class "Default")
      (node (ref "RS-232") (pin "7") (pinfunction "7_7") (pintype "passive"))
    )
    (net (code "181") (name "unconnected-(RS-232-Pad8)") (class "Default")
      (node (ref "RS-232") (pin "8") (pinfunction "8_8") (pintype "passive"))
    )
    (net (code "182") (name "unconnected-(RS-232-Pad9)") (class "Default")
      (node (ref "RS-232") (pin "9") (pinfunction "9_9") (pintype "passive"))
    )
    (net (code "183") (name "unconnected-(U1-ON{slash}OFF-Pad3)") (class "Default")
      (node (ref "U1") (pin "3") (pinfunction "ON/OFF_3") (pintype "input"))
    )
    (net (code "184") (name "~{MCLR}") (class "Default")
      (node (ref "IC9") (pin "7") (pinfunction "~{MCLR}_7") (pintype "input"))
      (node (ref "ICSP") (pin "1") (pinfunction "1_1") (pintype "passive"))
      (node (ref "R72") (pin "2") (pinfunction "2_2") (pintype "passive"))
    )
  )
)
